# 5000A_-_-v2_-_CT100.net
KiCad netlist of a schematic drawn in EasyEDA Pro
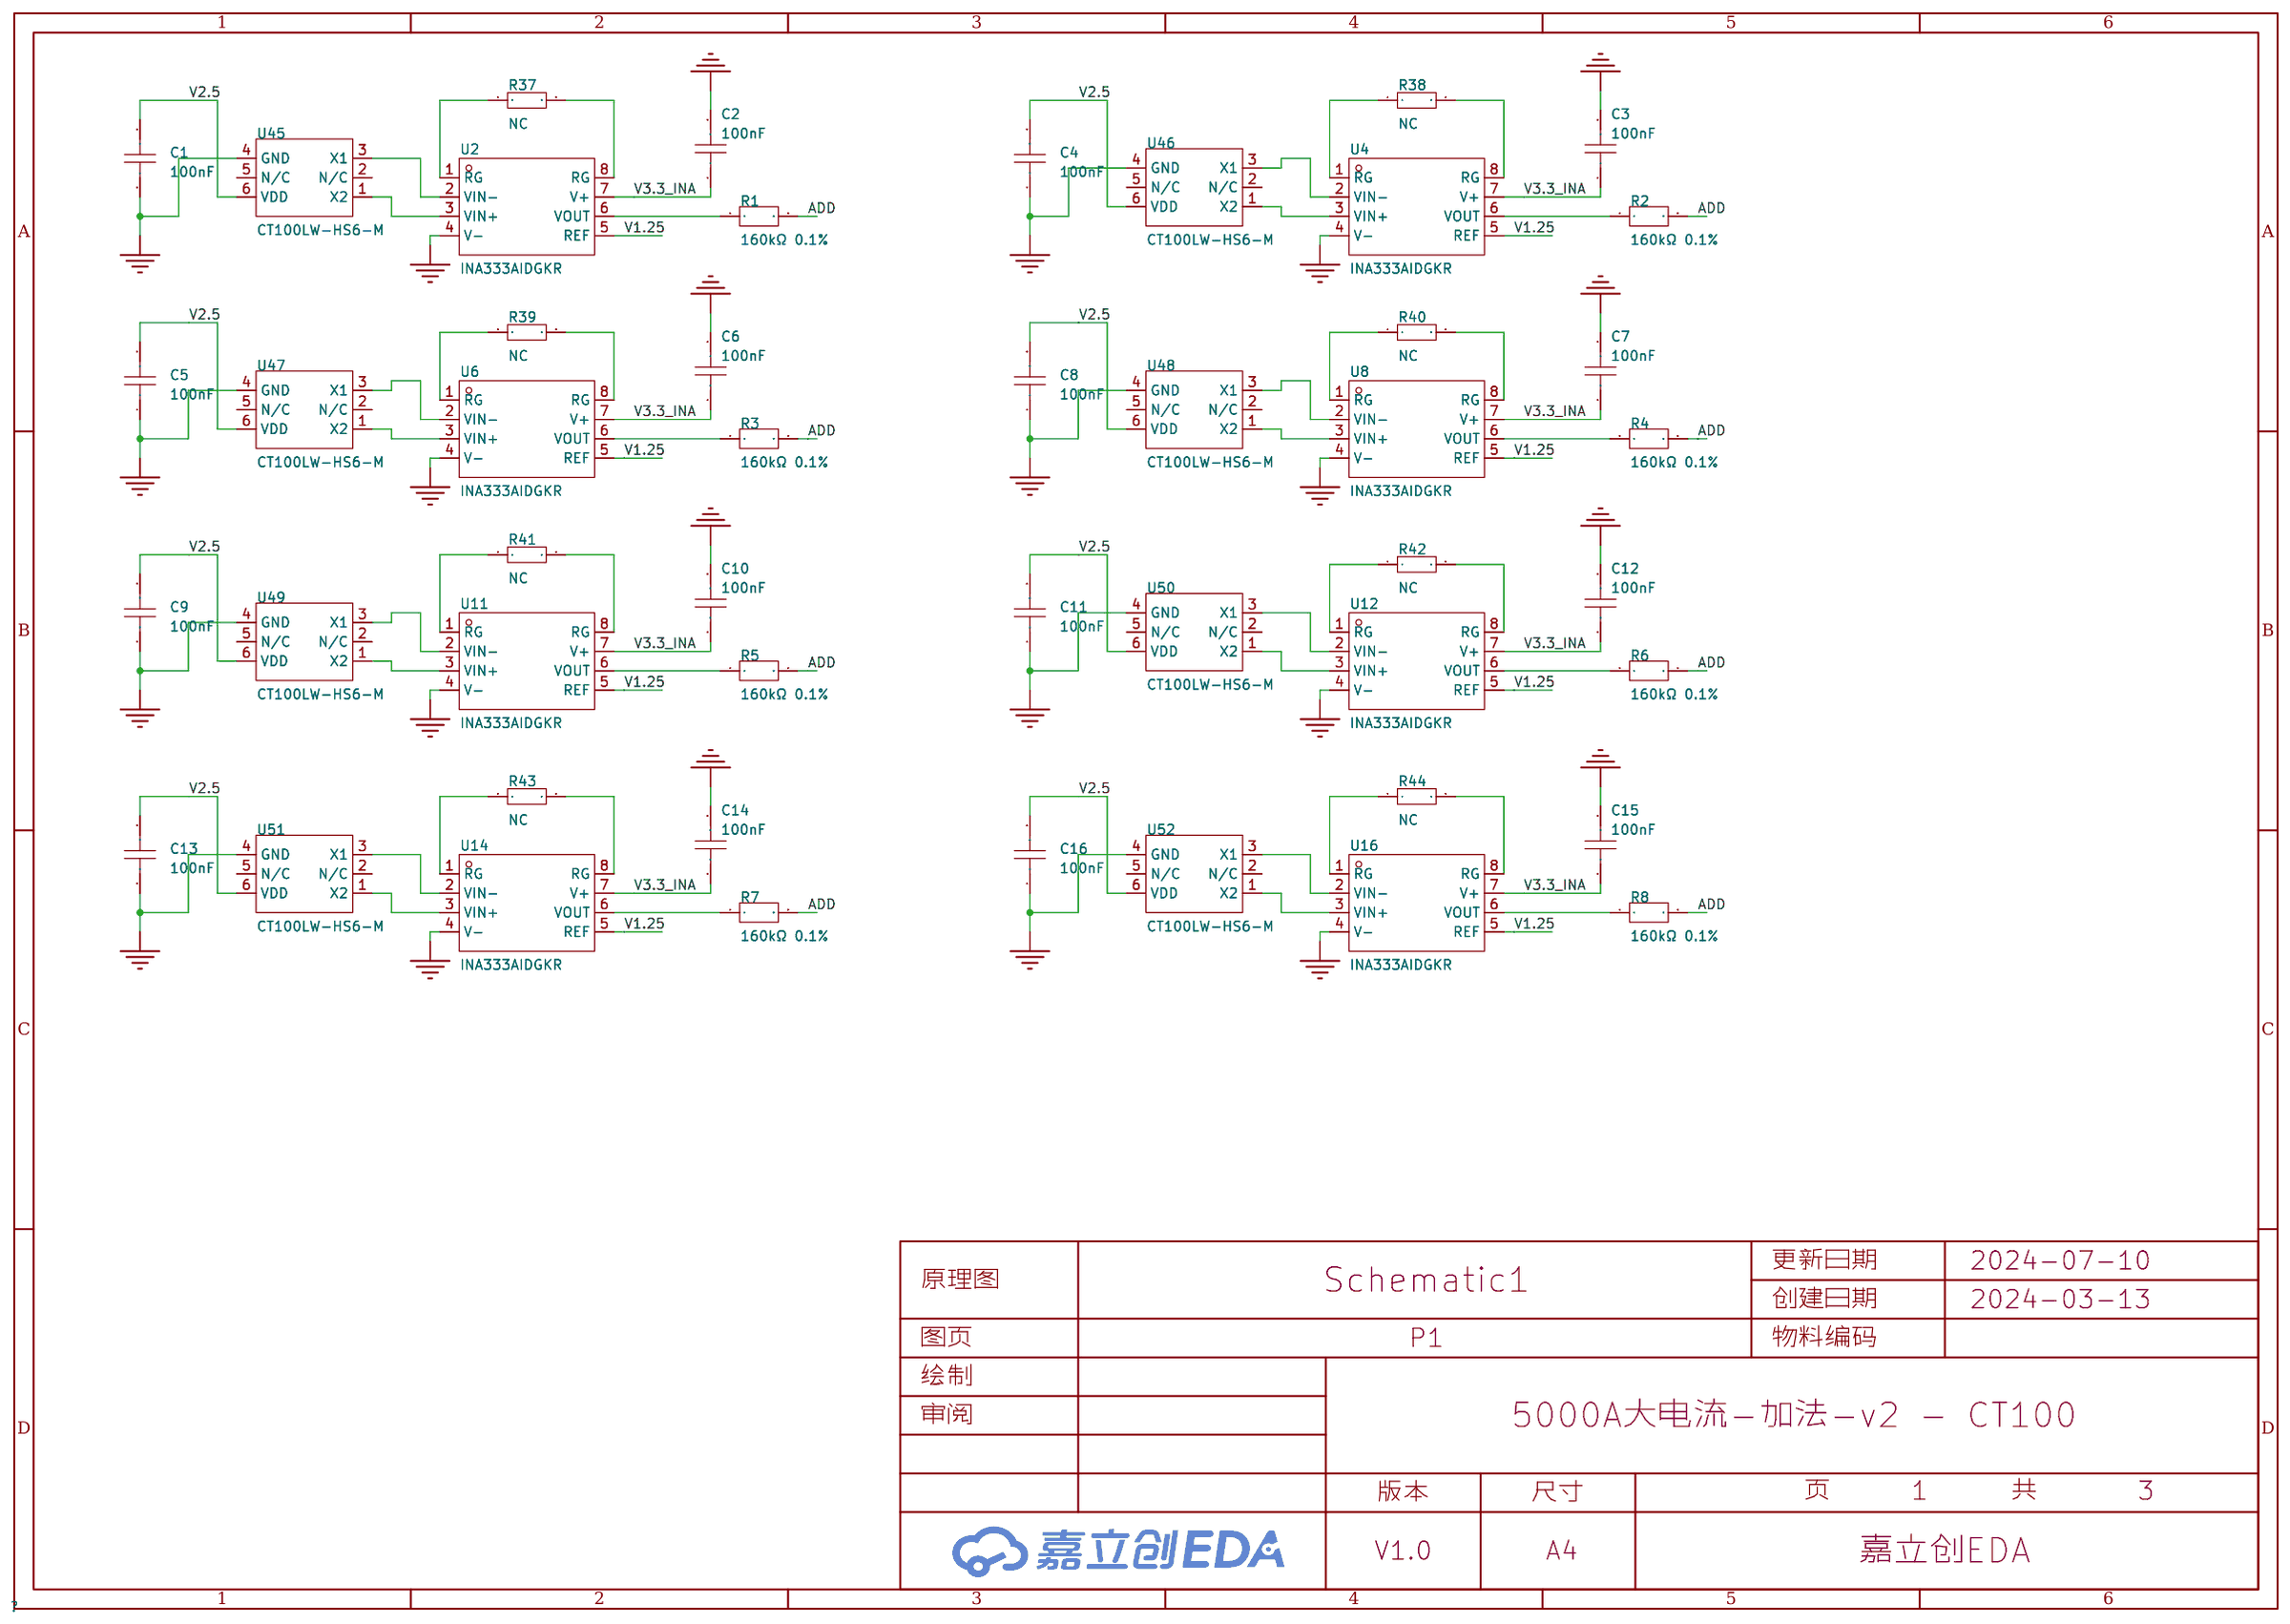
[diagram p0: P1]
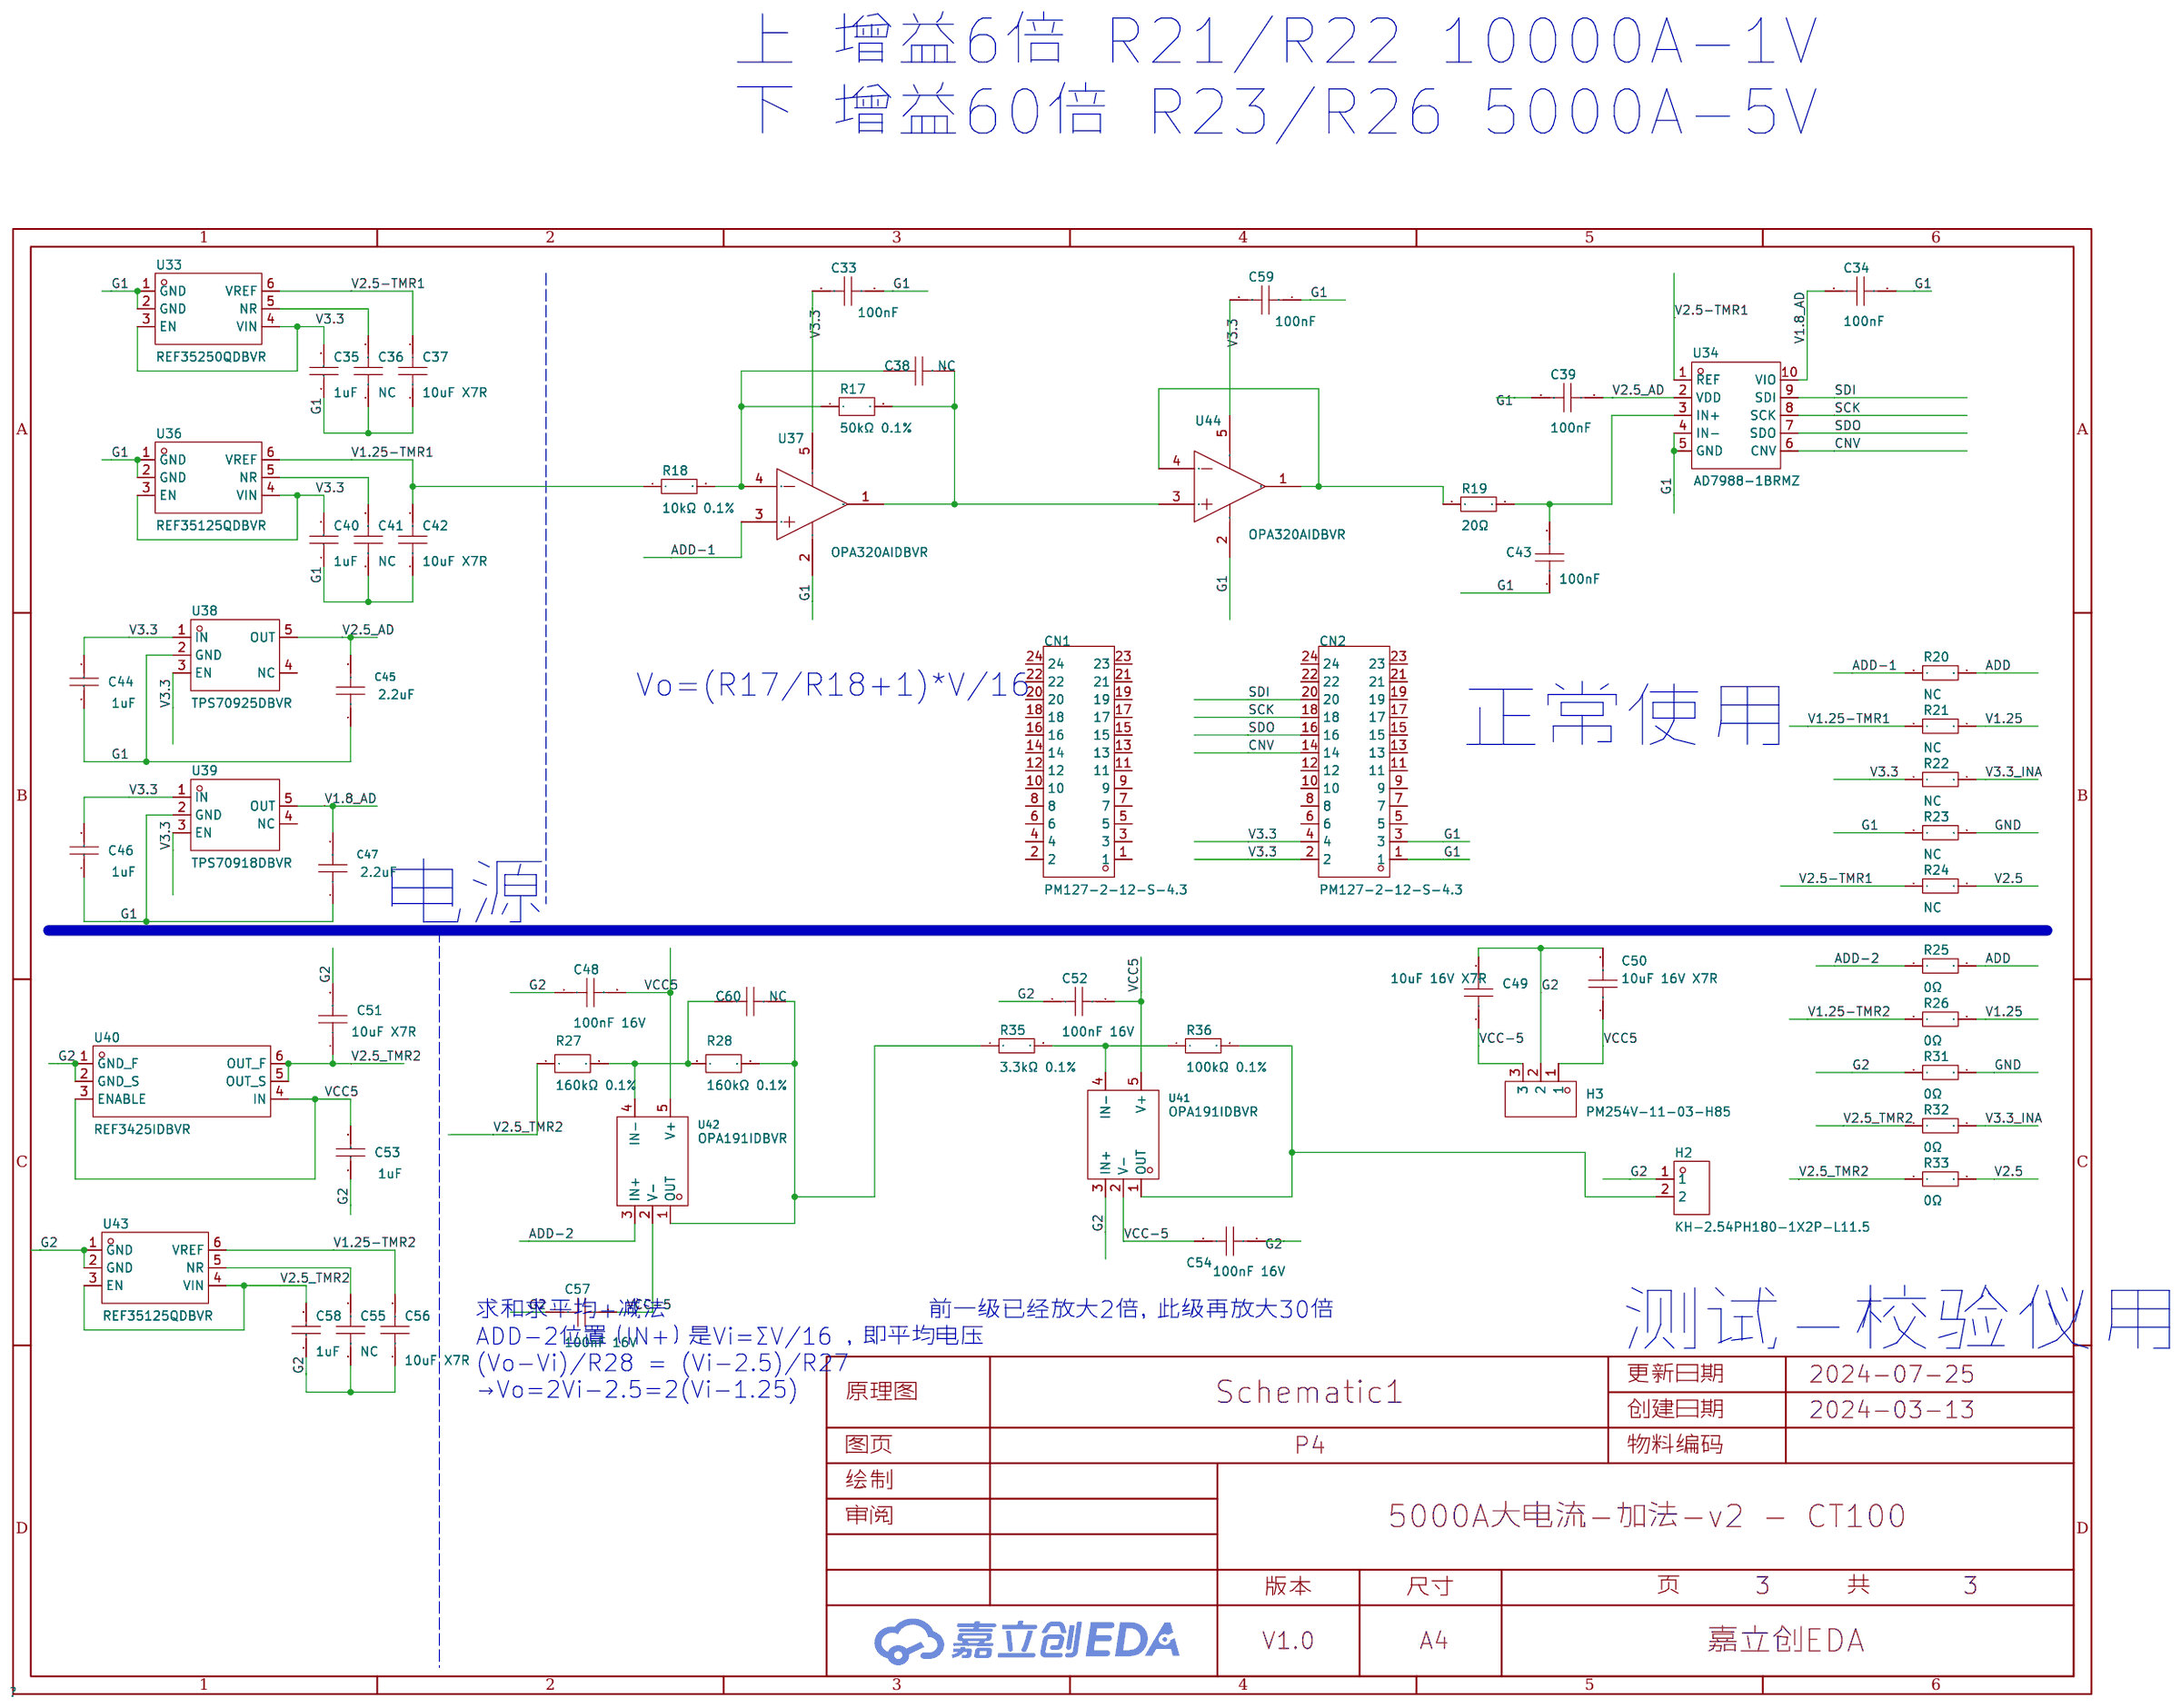
[diagram p1: P4]
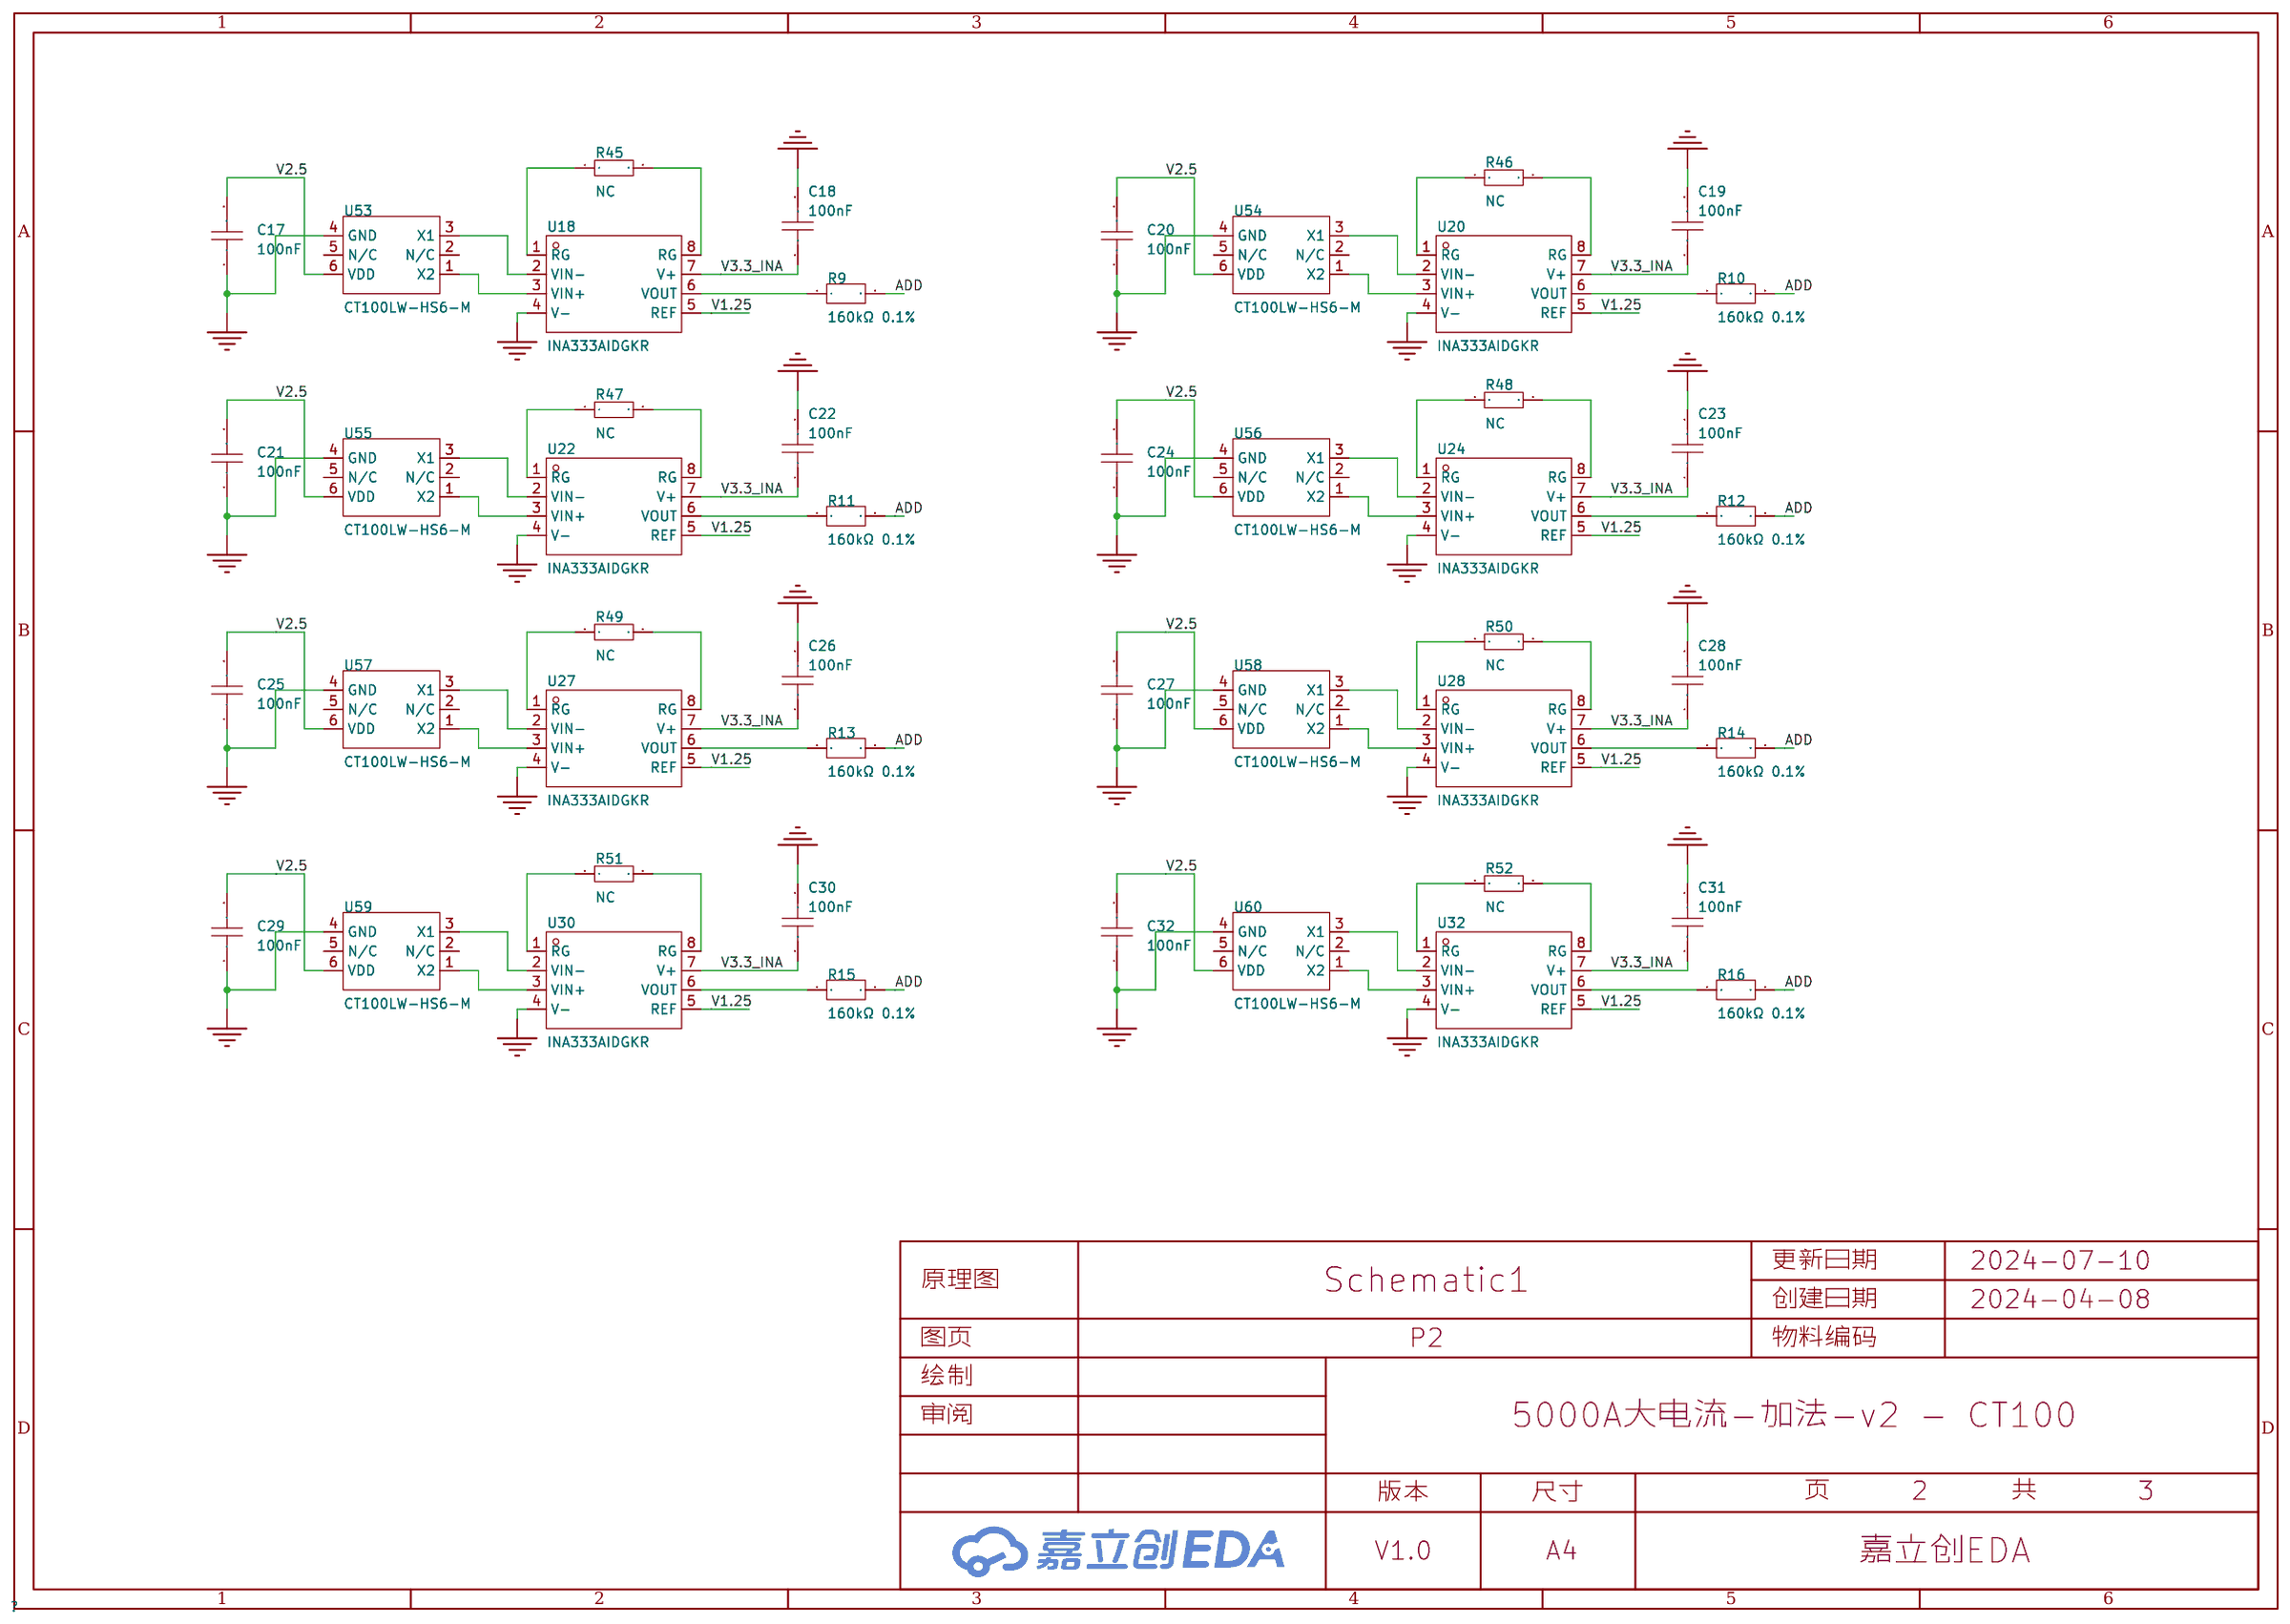
[diagram p2: P2]

(export (version "E")
  (design (tool "Eeschema 10.0.6"))
  (components
    (comp (ref "C1")
      (value "100nF")
      (footprint "easyedapro:C0603")
      (description "容值:100nF;精度:±10%;额定电压:10V;材质(温度系数):X7R;")
      (fields
        (field (name "Manufacturer Part") "CC0603KRX7R6BB104")
        (field (name "Manufacturer") "YAGEO(国巨)")
      )
      (libsource (lib "easyedapro") (part "CC0603KRX7R6BB104"))
    )
    (comp (ref "C2")
      (value "100nF")
      (footprint "easyedapro:C0603")
      (description "容值:100nF;精度:±10%;额定电压:10V;材质(温度系数):X7R;")
      (fields
        (field (name "Manufacturer Part") "CC0603KRX7R6BB104")
        (field (name "Manufacturer") "YAGEO(国巨)")
      )
      (libsource (lib "easyedapro") (part "CC0603KRX7R6BB104"))
    )
    (comp (ref "C3")
      (value "100nF")
      (footprint "easyedapro:C0603")
      (description "容值:100nF;精度:±10%;额定电压:10V;材质(温度系数):X7R;")
      (fields
        (field (name "Manufacturer Part") "CC0603KRX7R6BB104")
        (field (name "Manufacturer") "YAGEO(国巨)")
      )
      (libsource (lib "easyedapro") (part "CC0603KRX7R6BB104"))
    )
    (comp (ref "C4")
      (value "100nF")
      (footprint "easyedapro:C0603")
      (description "容值:100nF;精度:±10%;额定电压:10V;材质(温度系数):X7R;")
      (fields
        (field (name "Manufacturer Part") "CC0603KRX7R6BB104")
        (field (name "Manufacturer") "YAGEO(国巨)")
      )
      (libsource (lib "easyedapro") (part "CC0603KRX7R6BB104"))
    )
    (comp (ref "C5")
      (value "100nF")
      (footprint "easyedapro:C0603")
      (description "容值:100nF;精度:±10%;额定电压:10V;材质(温度系数):X7R;")
      (fields
        (field (name "Manufacturer Part") "CC0603KRX7R6BB104")
        (field (name "Manufacturer") "YAGEO(国巨)")
      )
      (libsource (lib "easyedapro") (part "CC0603KRX7R6BB104"))
    )
    (comp (ref "C6")
      (value "100nF")
      (footprint "easyedapro:C0603")
      (description "容值:100nF;精度:±10%;额定电压:10V;材质(温度系数):X7R;")
      (fields
        (field (name "Manufacturer Part") "CC0603KRX7R6BB104")
        (field (name "Manufacturer") "YAGEO(国巨)")
      )
      (libsource (lib "easyedapro") (part "CC0603KRX7R6BB104"))
    )
    (comp (ref "C7")
      (value "100nF")
      (footprint "easyedapro:C0603")
      (description "容值:100nF;精度:±10%;额定电压:10V;材质(温度系数):X7R;")
      (fields
        (field (name "Manufacturer Part") "CC0603KRX7R6BB104")
        (field (name "Manufacturer") "YAGEO(国巨)")
      )
      (libsource (lib "easyedapro") (part "CC0603KRX7R6BB104"))
    )
    (comp (ref "C8")
      (value "100nF")
      (footprint "easyedapro:C0603")
      (description "容值:100nF;精度:±10%;额定电压:10V;材质(温度系数):X7R;")
      (fields
        (field (name "Manufacturer Part") "CC0603KRX7R6BB104")
        (field (name "Manufacturer") "YAGEO(国巨)")
      )
      (libsource (lib "easyedapro") (part "CC0603KRX7R6BB104"))
    )
    (comp (ref "C9")
      (value "100nF")
      (footprint "easyedapro:C0603")
      (description "容值:100nF;精度:±10%;额定电压:10V;材质(温度系数):X7R;")
      (fields
        (field (name "Manufacturer Part") "CC0603KRX7R6BB104")
        (field (name "Manufacturer") "YAGEO(国巨)")
      )
      (libsource (lib "easyedapro") (part "CC0603KRX7R6BB104"))
    )
    (comp (ref "C10")
      (value "100nF")
      (footprint "easyedapro:C0603")
      (description "容值:100nF;精度:±10%;额定电压:10V;材质(温度系数):X7R;")
      (fields
        (field (name "Manufacturer Part") "CC0603KRX7R6BB104")
        (field (name "Manufacturer") "YAGEO(国巨)")
      )
      (libsource (lib "easyedapro") (part "CC0603KRX7R6BB104"))
    )
    (comp (ref "C11")
      (value "100nF")
      (footprint "easyedapro:C0603")
      (description "容值:100nF;精度:±10%;额定电压:10V;材质(温度系数):X7R;")
      (fields
        (field (name "Manufacturer Part") "CC0603KRX7R6BB104")
        (field (name "Manufacturer") "YAGEO(国巨)")
      )
      (libsource (lib "easyedapro") (part "CC0603KRX7R6BB104"))
    )
    (comp (ref "C12")
      (value "100nF")
      (footprint "easyedapro:C0603")
      (description "容值:100nF;精度:±10%;额定电压:10V;材质(温度系数):X7R;")
      (fields
        (field (name "Manufacturer Part") "CC0603KRX7R6BB104")
        (field (name "Manufacturer") "YAGEO(国巨)")
      )
      (libsource (lib "easyedapro") (part "CC0603KRX7R6BB104"))
    )
    (comp (ref "C13")
      (value "100nF")
      (footprint "easyedapro:C0603")
      (description "容值:100nF;精度:±10%;额定电压:10V;材质(温度系数):X7R;")
      (fields
        (field (name "Manufacturer Part") "CC0603KRX7R6BB104")
        (field (name "Manufacturer") "YAGEO(国巨)")
      )
      (libsource (lib "easyedapro") (part "CC0603KRX7R6BB104"))
    )
    (comp (ref "C14")
      (value "100nF")
      (footprint "easyedapro:C0603")
      (description "容值:100nF;精度:±10%;额定电压:10V;材质(温度系数):X7R;")
      (fields
        (field (name "Manufacturer Part") "CC0603KRX7R6BB104")
        (field (name "Manufacturer") "YAGEO(国巨)")
      )
      (libsource (lib "easyedapro") (part "CC0603KRX7R6BB104"))
    )
    (comp (ref "C15")
      (value "100nF")
      (footprint "easyedapro:C0603")
      (description "容值:100nF;精度:±10%;额定电压:10V;材质(温度系数):X7R;")
      (fields
        (field (name "Manufacturer Part") "CC0603KRX7R6BB104")
        (field (name "Manufacturer") "YAGEO(国巨)")
      )
      (libsource (lib "easyedapro") (part "CC0603KRX7R6BB104"))
    )
    (comp (ref "C16")
      (value "100nF")
      (footprint "easyedapro:C0603")
      (description "容值:100nF;精度:±10%;额定电压:10V;材质(温度系数):X7R;")
      (fields
        (field (name "Manufacturer Part") "CC0603KRX7R6BB104")
        (field (name "Manufacturer") "YAGEO(国巨)")
      )
      (libsource (lib "easyedapro") (part "CC0603KRX7R6BB104"))
    )
    (comp (ref "R1")
      (value "160kΩ 0.1%")
      (footprint "easyedapro:R0603")
      (description "电阻类型:薄膜电阻;阻值:160kΩ;精度:±0.1%;功率:100mW;最大工作电压:75V;温度系数:±25ppm/°C;")
      (fields (field (name "Manufacturer Part") "ERA3AEB164V") (field (name "Manufacturer") "PANASONIC(松下)"))
      (libsource (lib "easyedapro") (part "ERA3AEB164V"))
    )
    (comp (ref "R2")
      (value "160kΩ 0.1%")
      (footprint "easyedapro:R0603")
      (description "电阻类型:薄膜电阻;阻值:160kΩ;精度:±0.1%;功率:100mW;最大工作电压:75V;温度系数:±25ppm/°C;")
      (fields (field (name "Manufacturer Part") "ERA3AEB164V") (field (name "Manufacturer") "PANASONIC(松下)"))
      (libsource (lib "easyedapro") (part "ERA3AEB164V"))
    )
    (comp (ref "R3")
      (value "160kΩ 0.1%")
      (footprint "easyedapro:R0603")
      (description "电阻类型:薄膜电阻;阻值:160kΩ;精度:±0.1%;功率:100mW;最大工作电压:75V;温度系数:±25ppm/°C;")
      (fields (field (name "Manufacturer Part") "ERA3AEB164V") (field (name "Manufacturer") "PANASONIC(松下)"))
      (libsource (lib "easyedapro") (part "ERA3AEB164V"))
    )
    (comp (ref "R4")
      (value "160kΩ 0.1%")
      (footprint "easyedapro:R0603")
      (description "电阻类型:薄膜电阻;阻值:160kΩ;精度:±0.1%;功率:100mW;最大工作电压:75V;温度系数:±25ppm/°C;")
      (fields (field (name "Manufacturer Part") "ERA3AEB164V") (field (name "Manufacturer") "PANASONIC(松下)"))
      (libsource (lib "easyedapro") (part "ERA3AEB164V"))
    )
    (comp (ref "R5")
      (value "160kΩ 0.1%")
      (footprint "easyedapro:R0603")
      (description "电阻类型:薄膜电阻;阻值:160kΩ;精度:±0.1%;功率:100mW;最大工作电压:75V;温度系数:±25ppm/°C;")
      (fields (field (name "Manufacturer Part") "ERA3AEB164V") (field (name "Manufacturer") "PANASONIC(松下)"))
      (libsource (lib "easyedapro") (part "ERA3AEB164V"))
    )
    (comp (ref "R6")
      (value "160kΩ 0.1%")
      (footprint "easyedapro:R0603")
      (description "电阻类型:薄膜电阻;阻值:160kΩ;精度:±0.1%;功率:100mW;最大工作电压:75V;温度系数:±25ppm/°C;")
      (fields (field (name "Manufacturer Part") "ERA3AEB164V") (field (name "Manufacturer") "PANASONIC(松下)"))
      (libsource (lib "easyedapro") (part "ERA3AEB164V"))
    )
    (comp (ref "R7")
      (value "160kΩ 0.1%")
      (footprint "easyedapro:R0603")
      (description "电阻类型:薄膜电阻;阻值:160kΩ;精度:±0.1%;功率:100mW;最大工作电压:75V;温度系数:±25ppm/°C;")
      (fields (field (name "Manufacturer Part") "ERA3AEB164V") (field (name "Manufacturer") "PANASONIC(松下)"))
      (libsource (lib "easyedapro") (part "ERA3AEB164V"))
    )
    (comp (ref "R8")
      (value "160kΩ 0.1%")
      (footprint "easyedapro:R0603")
      (description "电阻类型:薄膜电阻;阻值:160kΩ;精度:±0.1%;功率:100mW;最大工作电压:75V;温度系数:±25ppm/°C;")
      (fields (field (name "Manufacturer Part") "ERA3AEB164V") (field (name "Manufacturer") "PANASONIC(松下)"))
      (libsource (lib "easyedapro") (part "ERA3AEB164V"))
    )
    (comp (ref "R37") (value "NC") (footprint "easyedapro:R0603") (libsource (lib "easyedapro") (part "电阻")))
    (comp (ref "R38") (value "NC") (footprint "easyedapro:R0603") (libsource (lib "easyedapro") (part "电阻")))
    (comp (ref "R39") (value "NC") (footprint "easyedapro:R0603") (libsource (lib "easyedapro") (part "电阻")))
    (comp (ref "R40") (value "NC") (footprint "easyedapro:R0603") (libsource (lib "easyedapro") (part "电阻")))
    (comp (ref "R41") (value "NC") (footprint "easyedapro:R0603") (libsource (lib "easyedapro") (part "电阻")))
    (comp (ref "R42") (value "NC") (footprint "easyedapro:R0603") (libsource (lib "easyedapro") (part "电阻")))
    (comp (ref "R43") (value "NC") (footprint "easyedapro:R0603") (libsource (lib "easyedapro") (part "电阻")))
    (comp (ref "R44") (value "NC") (footprint "easyedapro:R0603") (libsource (lib "easyedapro") (part "电阻")))
    (comp (ref "U2")
      (value "INA333AIDGKR")
      (footprint "easyedapro:MSOP-8_L3.0-W3.0-P0.65-LS5.0-BL")
      (description "放大器数:单路;输入偏置电流(Ib):70pA;输入失调电压(Vos):10uV;压摆率(SR):0.16V/us;带宽(-3db):150kHz;轨到轨:-;")
      (fields (field (name "Manufacturer") "TI(德州仪器)"))
      (libsource (lib "easyedapro") (part "INA333AIDGKR"))
    )
    (comp (ref "U4")
      (value "INA333AIDGKR")
      (footprint "easyedapro:MSOP-8_L3.0-W3.0-P0.65-LS5.0-BL")
      (description "放大器数:单路;输入偏置电流(Ib):70pA;输入失调电压(Vos):10uV;压摆率(SR):0.16V/us;带宽(-3db):150kHz;轨到轨:-;")
      (fields (field (name "Manufacturer") "TI(德州仪器)"))
      (libsource (lib "easyedapro") (part "INA333AIDGKR"))
    )
    (comp (ref "U6")
      (value "INA333AIDGKR")
      (footprint "easyedapro:MSOP-8_L3.0-W3.0-P0.65-LS5.0-BL")
      (description "放大器数:单路;输入偏置电流(Ib):70pA;输入失调电压(Vos):10uV;压摆率(SR):0.16V/us;带宽(-3db):150kHz;轨到轨:-;")
      (fields (field (name "Manufacturer") "TI(德州仪器)"))
      (libsource (lib "easyedapro") (part "INA333AIDGKR"))
    )
    (comp (ref "U8")
      (value "INA333AIDGKR")
      (footprint "easyedapro:MSOP-8_L3.0-W3.0-P0.65-LS5.0-BL")
      (description "放大器数:单路;输入偏置电流(Ib):70pA;输入失调电压(Vos):10uV;压摆率(SR):0.16V/us;带宽(-3db):150kHz;轨到轨:-;")
      (fields (field (name "Manufacturer") "TI(德州仪器)"))
      (libsource (lib "easyedapro") (part "INA333AIDGKR"))
    )
    (comp (ref "U11")
      (value "INA333AIDGKR")
      (footprint "easyedapro:MSOP-8_L3.0-W3.0-P0.65-LS5.0-BL")
      (description "放大器数:单路;输入偏置电流(Ib):70pA;输入失调电压(Vos):10uV;压摆率(SR):0.16V/us;带宽(-3db):150kHz;轨到轨:-;")
      (fields (field (name "Manufacturer") "TI(德州仪器)"))
      (libsource (lib "easyedapro") (part "INA333AIDGKR"))
    )
    (comp (ref "U12")
      (value "INA333AIDGKR")
      (footprint "easyedapro:MSOP-8_L3.0-W3.0-P0.65-LS5.0-BL")
      (description "放大器数:单路;输入偏置电流(Ib):70pA;输入失调电压(Vos):10uV;压摆率(SR):0.16V/us;带宽(-3db):150kHz;轨到轨:-;")
      (fields (field (name "Manufacturer") "TI(德州仪器)"))
      (libsource (lib "easyedapro") (part "INA333AIDGKR"))
    )
    (comp (ref "U14")
      (value "INA333AIDGKR")
      (footprint "easyedapro:MSOP-8_L3.0-W3.0-P0.65-LS5.0-BL")
      (description "放大器数:单路;输入偏置电流(Ib):70pA;输入失调电压(Vos):10uV;压摆率(SR):0.16V/us;带宽(-3db):150kHz;轨到轨:-;")
      (fields (field (name "Manufacturer") "TI(德州仪器)"))
      (libsource (lib "easyedapro") (part "INA333AIDGKR"))
    )
    (comp (ref "U16")
      (value "INA333AIDGKR")
      (footprint "easyedapro:MSOP-8_L3.0-W3.0-P0.65-LS5.0-BL")
      (description "放大器数:单路;输入偏置电流(Ib):70pA;输入失调电压(Vos):10uV;压摆率(SR):0.16V/us;带宽(-3db):150kHz;轨到轨:-;")
      (fields (field (name "Manufacturer") "TI(德州仪器)"))
      (libsource (lib "easyedapro") (part "INA333AIDGKR"))
    )
    (comp (ref "U45")
      (value "CT100LW-HS6-M")
      (footprint "easyedapro:TSOT-23-6_L2.9-W1.6-P0.95-LS2.8-BL")
      (description "工作点(Gs):-;释放点(Gs):-;")
      (fields (field (name "Manufacturer") "muRata(村田)"))
      (libsource (lib "easyedapro") (part "CT100LW-HS6-M"))
    )
    (comp (ref "U46")
      (value "CT100LW-HS6-M")
      (footprint "easyedapro:TSOT-23-6_L2.9-W1.6-P0.95-LS2.8-BL")
      (description "工作点(Gs):-;释放点(Gs):-;")
      (fields (field (name "Manufacturer") "muRata(村田)"))
      (libsource (lib "easyedapro") (part "CT100LW-HS6-M"))
    )
    (comp (ref "U47")
      (value "CT100LW-HS6-M")
      (footprint "easyedapro:TSOT-23-6_L2.9-W1.6-P0.95-LS2.8-BL")
      (description "工作点(Gs):-;释放点(Gs):-;")
      (fields (field (name "Manufacturer") "muRata(村田)"))
      (libsource (lib "easyedapro") (part "CT100LW-HS6-M"))
    )
    (comp (ref "U48")
      (value "CT100LW-HS6-M")
      (footprint "easyedapro:TSOT-23-6_L2.9-W1.6-P0.95-LS2.8-BL")
      (description "工作点(Gs):-;释放点(Gs):-;")
      (fields (field (name "Manufacturer") "muRata(村田)"))
      (libsource (lib "easyedapro") (part "CT100LW-HS6-M"))
    )
    (comp (ref "U49")
      (value "CT100LW-HS6-M")
      (footprint "easyedapro:TSOT-23-6_L2.9-W1.6-P0.95-LS2.8-BL")
      (description "工作点(Gs):-;释放点(Gs):-;")
      (fields (field (name "Manufacturer") "muRata(村田)"))
      (libsource (lib "easyedapro") (part "CT100LW-HS6-M"))
    )
    (comp (ref "U50")
      (value "CT100LW-HS6-M")
      (footprint "easyedapro:TSOT-23-6_L2.9-W1.6-P0.95-LS2.8-BL")
      (description "工作点(Gs):-;释放点(Gs):-;")
      (fields (field (name "Manufacturer") "muRata(村田)"))
      (libsource (lib "easyedapro") (part "CT100LW-HS6-M"))
    )
    (comp (ref "U51")
      (value "CT100LW-HS6-M")
      (footprint "easyedapro:TSOT-23-6_L2.9-W1.6-P0.95-LS2.8-BL")
      (description "工作点(Gs):-;释放点(Gs):-;")
      (fields (field (name "Manufacturer") "muRata(村田)"))
      (libsource (lib "easyedapro") (part "CT100LW-HS6-M"))
    )
    (comp (ref "U52")
      (value "CT100LW-HS6-M")
      (footprint "easyedapro:TSOT-23-6_L2.9-W1.6-P0.95-LS2.8-BL")
      (description "工作点(Gs):-;释放点(Gs):-;")
      (fields (field (name "Manufacturer") "muRata(村田)"))
      (libsource (lib "easyedapro") (part "CT100LW-HS6-M"))
    )
    (comp (ref "C33")
      (value "100nF")
      (footprint "easyedapro:C0603")
      (description "容值:100nF;精度:±10%;额定电压:10V;材质(温度系数):X7R;")
      (fields
        (field (name "Manufacturer Part") "CC0603KRX7R6BB104")
        (field (name "Manufacturer") "YAGEO(国巨)")
      )
      (libsource (lib "easyedapro") (part "CC0603KRX7R6BB104"))
    )
    (comp (ref "C34")
      (value "100nF")
      (footprint "easyedapro:C0603")
      (description "容值:100nF;精度:±10%;额定电压:10V;材质(温度系数):X7R;")
      (fields
        (field (name "Manufacturer Part") "CC0603KRX7R6BB104")
        (field (name "Manufacturer") "YAGEO(国巨)")
      )
      (libsource (lib "easyedapro") (part "CC0603KRX7R6BB104"))
    )
    (comp (ref "C35")
      (value "1uF")
      (footprint "easyedapro:C0603")
      (description "容值:1uF;精度:±10%;额定电压:25V;材质(温度系数):X7R;")
      (fields (field (name "Manufacturer Part") "0603B105K250NT") (field (name "Manufacturer") "FH(风华)"))
      (libsource (lib "easyedapro") (part "0603B105K250NT"))
    )
    (comp (ref "C36")
      (value "NC")
      (footprint "easyedapro:C0603")
      (description "容值:10uF;精度:±10%;额定电压:10V;材质(温度系数):X7R;")
      (fields
        (field (name "Manufacturer Part") "GRM188Z71A106KA73D")
        (field (name "Manufacturer") "muRata(村田)")
      )
      (libsource (lib "easyedapro") (part "GRM188Z71A106KA73D"))
    )
    (comp (ref "C37")
      (value "10uF X7R")
      (footprint "easyedapro:C0603")
      (description "容值:10uF;精度:±10%;额定电压:10V;材质(温度系数):X7R;")
      (fields
        (field (name "Manufacturer Part") "GRM188Z71A106KA73D")
        (field (name "Manufacturer") "muRata(村田)")
      )
      (libsource (lib "easyedapro") (part "GRM188Z71A106KA73D"))
    )
    (comp (ref "C38")
      (value "NC")
      (footprint "easyedapro:C0603")
      (libsource (lib "easyedapro") (part "CapAcitance"))
    )
    (comp (ref "C39")
      (value "100nF")
      (footprint "easyedapro:C0603")
      (description "容值:100nF;精度:±10%;额定电压:10V;材质(温度系数):X7R;")
      (fields
        (field (name "Manufacturer Part") "CC0603KRX7R6BB104")
        (field (name "Manufacturer") "YAGEO(国巨)")
      )
      (libsource (lib "easyedapro") (part "CC0603KRX7R6BB104"))
    )
    (comp (ref "C40")
      (value "1uF")
      (footprint "easyedapro:C0603")
      (description "容值:1uF;精度:±10%;额定电压:25V;材质(温度系数):X7R;")
      (fields (field (name "Manufacturer Part") "0603B105K250NT") (field (name "Manufacturer") "FH(风华)"))
      (libsource (lib "easyedapro") (part "0603B105K250NT"))
    )
    (comp (ref "C41")
      (value "NC")
      (footprint "easyedapro:C0603")
      (description "容值:10uF;精度:±10%;额定电压:10V;材质(温度系数):X7R;")
      (fields
        (field (name "Manufacturer Part") "GRM188Z71A106KA73D")
        (field (name "Manufacturer") "muRata(村田)")
      )
      (libsource (lib "easyedapro") (part "GRM188Z71A106KA73D"))
    )
    (comp (ref "C42")
      (value "10uF X7R")
      (footprint "easyedapro:C0603")
      (description "容值:10uF;精度:±10%;额定电压:10V;材质(温度系数):X7R;")
      (fields
        (field (name "Manufacturer Part") "GRM188Z71A106KA73D")
        (field (name "Manufacturer") "muRata(村田)")
      )
      (libsource (lib "easyedapro") (part "GRM188Z71A106KA73D"))
    )
    (comp (ref "C43")
      (value "100nF")
      (footprint "easyedapro:C0603")
      (description "容值:100nF;精度:±10%;额定电压:10V;材质(温度系数):X7R;")
      (fields
        (field (name "Manufacturer Part") "CC0603KRX7R6BB104")
        (field (name "Manufacturer") "YAGEO(国巨)")
      )
      (libsource (lib "easyedapro") (part "CC0603KRX7R6BB104"))
    )
    (comp (ref "C44")
      (value "1uF")
      (footprint "easyedapro:C0603")
      (description "容值:1uF;精度:±10%;额定电压:25V;材质(温度系数):X7R;")
      (fields (field (name "Manufacturer Part") "0603B105K250NT") (field (name "Manufacturer") "FH(风华)"))
      (libsource (lib "easyedapro") (part "0603B105K250NT"))
    )
    (comp (ref "C45")
      (value "2.2uF")
      (footprint "easyedapro:C0603")
      (description "容值:2.2uF;精度:±10%;额定电压:50V;材质(温度系数):X5R;")
      (fields
        (field (name "Manufacturer Part") "CL10A225KB8NNNC")
        (field (name "Manufacturer") "SAMSUNG(三星)")
      )
      (libsource (lib "easyedapro") (part "CL10A225KB8NNNC"))
    )
    (comp (ref "C46")
      (value "1uF")
      (footprint "easyedapro:C0603")
      (description "容值:1uF;精度:±10%;额定电压:25V;材质(温度系数):X7R;")
      (fields (field (name "Manufacturer Part") "0603B105K250NT") (field (name "Manufacturer") "FH(风华)"))
      (libsource (lib "easyedapro") (part "0603B105K250NT"))
    )
    (comp (ref "C47")
      (value "2.2uF")
      (footprint "easyedapro:C0603")
      (description "容值:2.2uF;精度:±10%;额定电压:50V;材质(温度系数):X5R;")
      (fields
        (field (name "Manufacturer Part") "CL10A225KB8NNNC")
        (field (name "Manufacturer") "SAMSUNG(三星)")
      )
      (libsource (lib "easyedapro") (part "CL10A225KB8NNNC"))
    )
    (comp (ref "C48")
      (value "100nF 16V")
      (footprint "easyedapro:C0603")
      (description "容值:100nF;精度:±10%;额定电压:10V;材质(温度系数):X7R;")
      (fields
        (field (name "Manufacturer Part") "CC0603KRX7R6BB104")
        (field (name "Manufacturer") "YAGEO(国巨)")
      )
      (libsource (lib "easyedapro") (part "CC0603KRX7R6BB104"))
    )
    (comp (ref "C49")
      (value "10uF 16V X7R")
      (footprint "easyedapro:C0603")
      (description "容值:10uF;精度:±10%;额定电压:10V;材质(温度系数):X7R;")
      (fields
        (field (name "Manufacturer Part") "GRM188Z71A106KA73D")
        (field (name "Manufacturer") "muRata(村田)")
      )
      (libsource (lib "easyedapro") (part "GRM188Z71A106KA73D"))
    )
    (comp (ref "C50")
      (value "10uF 16V X7R")
      (footprint "easyedapro:C0603")
      (description "容值:10uF;精度:±10%;额定电压:10V;材质(温度系数):X7R;")
      (fields
        (field (name "Manufacturer Part") "GRM188Z71A106KA73D")
        (field (name "Manufacturer") "muRata(村田)")
      )
      (libsource (lib "easyedapro") (part "GRM188Z71A106KA73D"))
    )
    (comp (ref "C51")
      (value "10uF X7R")
      (footprint "easyedapro:C0603")
      (description "容值:10uF;精度:±10%;额定电压:10V;材质(温度系数):X7R;")
      (fields
        (field (name "Manufacturer Part") "GRM188Z71A106KA73D")
        (field (name "Manufacturer") "muRata(村田)")
      )
      (libsource (lib "easyedapro") (part "GRM188Z71A106KA73D"))
    )
    (comp (ref "C52")
      (value "100nF 16V")
      (footprint "easyedapro:C0603")
      (description "容值:100nF;精度:±10%;额定电压:10V;材质(温度系数):X7R;")
      (fields
        (field (name "Manufacturer Part") "CC0603KRX7R6BB104")
        (field (name "Manufacturer") "YAGEO(国巨)")
      )
      (libsource (lib "easyedapro") (part "CC0603KRX7R6BB104"))
    )
    (comp (ref "C53")
      (value "1uF")
      (footprint "easyedapro:C0603")
      (description "容值:1uF;精度:±10%;额定电压:25V;材质(温度系数):X7R;")
      (fields (field (name "Manufacturer Part") "0603B105K250NT") (field (name "Manufacturer") "FH(风华)"))
      (libsource (lib "easyedapro") (part "0603B105K250NT"))
    )
    (comp (ref "C54")
      (value "100nF 16V")
      (footprint "easyedapro:C0603")
      (description "容值:100nF;精度:±10%;额定电压:10V;材质(温度系数):X7R;")
      (fields
        (field (name "Manufacturer Part") "CC0603KRX7R6BB104")
        (field (name "Manufacturer") "YAGEO(国巨)")
      )
      (libsource (lib "easyedapro") (part "CC0603KRX7R6BB104"))
    )
    (comp (ref "C55")
      (value "NC")
      (footprint "easyedapro:C0603")
      (description "容值:10uF;精度:±10%;额定电压:10V;材质(温度系数):X7R;")
      (fields
        (field (name "Manufacturer Part") "GRM188Z71A106KA73D")
        (field (name "Manufacturer") "muRata(村田)")
      )
      (libsource (lib "easyedapro") (part "GRM188Z71A106KA73D"))
    )
    (comp (ref "C56")
      (value "10uF X7R")
      (footprint "easyedapro:C0603")
      (description "容值:10uF;精度:±10%;额定电压:10V;材质(温度系数):X7R;")
      (fields
        (field (name "Manufacturer Part") "GRM188Z71A106KA73D")
        (field (name "Manufacturer") "muRata(村田)")
      )
      (libsource (lib "easyedapro") (part "GRM188Z71A106KA73D"))
    )
    (comp (ref "C57")
      (value "100nF 16V")
      (footprint "easyedapro:C0603")
      (description "容值:100nF;精度:±10%;额定电压:10V;材质(温度系数):X7R;")
      (fields
        (field (name "Manufacturer Part") "CC0603KRX7R6BB104")
        (field (name "Manufacturer") "YAGEO(国巨)")
      )
      (libsource (lib "easyedapro") (part "CC0603KRX7R6BB104"))
    )
    (comp (ref "C58")
      (value "1uF")
      (footprint "easyedapro:C0603")
      (description "容值:1uF;精度:±10%;额定电压:25V;材质(温度系数):X7R;")
      (fields (field (name "Manufacturer Part") "0603B105K250NT") (field (name "Manufacturer") "FH(风华)"))
      (libsource (lib "easyedapro") (part "0603B105K250NT"))
    )
    (comp (ref "C59")
      (value "100nF")
      (footprint "easyedapro:C0603")
      (description "容值:100nF;精度:±10%;额定电压:10V;材质(温度系数):X7R;")
      (fields
        (field (name "Manufacturer Part") "CC0603KRX7R6BB104")
        (field (name "Manufacturer") "YAGEO(国巨)")
      )
      (libsource (lib "easyedapro") (part "CC0603KRX7R6BB104"))
    )
    (comp (ref "C60")
      (value "NC")
      (footprint "easyedapro:C0603")
      (libsource (lib "easyedapro") (part "CapAcitance"))
    )
    (comp (ref "CN1")
      (value "PM127-2-12-S-4.3")
      (footprint "easyedapro:HDR-SMD_24P-P1.27-V-F-R2-C12-LS4.8")
      (fields (field (name "Manufacturer") "HCTL(华灿天禄)"))
      (libsource (lib "easyedapro") (part "PM127-2-12-S-4.3"))
    )
    (comp (ref "CN2")
      (value "PM127-2-12-S-4.3")
      (footprint "easyedapro:HDR-SMD_24P-P1.27-V-F-R2-C12-LS4.8")
      (fields (field (name "Manufacturer") "HCTL(华灿天禄)"))
      (libsource (lib "easyedapro") (part "PM127-2-12-S-4.3"))
    )
    (comp (ref "H2")
      (value "KH-2.54PH180-1X2P-L11.5")
      (footprint "easyedapro:HDR-TH_2P-P2.54-V-M")
      (fields (field (name "Manufacturer") "kinghelm(金航标)"))
      (libsource (lib "easyedapro") (part "KH-2.54PH180-1X2P-L11.5"))
    )
    (comp (ref "H3")
      (value "PM254V-11-03-H85")
      (footprint "easyedapro:HDR-TH_3P-P2.54-V-F")
      (description "插孔结构:1x3P;间距:2.54mm;行距:-;安装类型:直插;排数:单排;总孔位数:3P;塑高:-;触头材质:黄铜;触头镀层:-;")
      (fields (field (name "Manufacturer") "XFCN(兴飞)"))
      (libsource (lib "easyedapro") (part "PM254V-11-03-H85"))
    )
    (comp (ref "R17")
      (value "50kΩ 0.1%")
      (footprint "easyedapro:R0603")
      (description "电阻类型:薄膜电阻;阻值:50kΩ;精度:±0.1%;功率:100mW;最大工作电压:-;温度系数:±25ppm/°C;")
      (fields (field (name "Manufacturer Part") "RT0603BRD0750KL") (field (name "Manufacturer") "YAGEO(国巨)"))
      (libsource (lib "easyedapro") (part "RT0603BRD0750KL"))
    )
    (comp (ref "R18")
      (value "10kΩ 0.1%")
      (footprint "easyedapro:R0603")
      (description "电阻类型:薄膜电阻;阻值:10kΩ;精度:±0.1%;功率:100mW;最大工作电压:75V;温度系数:±25ppm/°C;")
      (fields (field (name "Manufacturer Part") "RT0603BRD0710KL") (field (name "Manufacturer") "YAGEO(国巨)"))
      (libsource (lib "easyedapro") (part "RT0603BRD0710KL"))
    )
    (comp (ref "R19")
      (value "20Ω")
      (footprint "easyedapro:R0603")
      (description "电阻类型:厚膜电阻;阻值:20Ω;精度:±1%;功率:100mW;最大工作电压:75V;温度系数:±100ppm/°C;")
      (fields (field (name "Manufacturer Part") "RC0603FR-0720RL") (field (name "Manufacturer") "YAGEO(国巨)"))
      (libsource (lib "easyedapro") (part "RC0603FR-0720RL"))
    )
    (comp (ref "R20")
      (value "NC")
      (footprint "easyedapro:R0603")
      (description "电阻类型:厚膜电阻;阻值:0Ω;精度:±1%;功率:100mW;最大工作电压:75V;")
      (fields
        (field (name "Manufacturer Part") "0603WAF0000T5E")
        (field (name "Manufacturer") "UNI-ROYAL(厚声)")
      )
      (libsource (lib "easyedapro") (part "0603WAF0000T5E"))
    )
    (comp (ref "R21")
      (value "NC")
      (footprint "easyedapro:R0603")
      (description "电阻类型:厚膜电阻;阻值:0Ω;精度:±1%;功率:100mW;最大工作电压:75V;")
      (fields
        (field (name "Manufacturer Part") "0603WAF0000T5E")
        (field (name "Manufacturer") "UNI-ROYAL(厚声)")
      )
      (libsource (lib "easyedapro") (part "0603WAF0000T5E"))
    )
    (comp (ref "R22")
      (value "NC")
      (footprint "easyedapro:R0603")
      (description "电阻类型:厚膜电阻;阻值:0Ω;精度:±1%;功率:100mW;最大工作电压:75V;")
      (fields
        (field (name "Manufacturer Part") "0603WAF0000T5E")
        (field (name "Manufacturer") "UNI-ROYAL(厚声)")
      )
      (libsource (lib "easyedapro") (part "0603WAF0000T5E"))
    )
    (comp (ref "R23")
      (value "NC")
      (footprint "easyedapro:R0603")
      (description "电阻类型:厚膜电阻;阻值:0Ω;精度:±1%;功率:100mW;最大工作电压:75V;")
      (fields
        (field (name "Manufacturer Part") "0603WAF0000T5E")
        (field (name "Manufacturer") "UNI-ROYAL(厚声)")
      )
      (libsource (lib "easyedapro") (part "0603WAF0000T5E"))
    )
    (comp (ref "R24")
      (value "NC")
      (footprint "easyedapro:R0603")
      (description "电阻类型:厚膜电阻;阻值:0Ω;精度:±1%;功率:100mW;最大工作电压:75V;")
      (fields
        (field (name "Manufacturer Part") "0603WAF0000T5E")
        (field (name "Manufacturer") "UNI-ROYAL(厚声)")
      )
      (libsource (lib "easyedapro") (part "0603WAF0000T5E"))
    )
    (comp (ref "R25")
      (value "0Ω")
      (footprint "easyedapro:R0603")
      (description "电阻类型:厚膜电阻;阻值:0Ω;精度:±1%;功率:100mW;最大工作电压:75V;")
      (fields
        (field (name "Manufacturer Part") "0603WAF0000T5E")
        (field (name "Manufacturer") "UNI-ROYAL(厚声)")
      )
      (libsource (lib "easyedapro") (part "0603WAF0000T5E"))
    )
    (comp (ref "R26")
      (value "0Ω")
      (footprint "easyedapro:R0603")
      (description "电阻类型:厚膜电阻;阻值:0Ω;精度:±1%;功率:100mW;最大工作电压:75V;")
      (fields
        (field (name "Manufacturer Part") "0603WAF0000T5E")
        (field (name "Manufacturer") "UNI-ROYAL(厚声)")
      )
      (libsource (lib "easyedapro") (part "0603WAF0000T5E"))
    )
    (comp (ref "R27")
      (value "160kΩ 0.1%")
      (footprint "easyedapro:R0603")
      (description "电阻类型:薄膜电阻;阻值:160kΩ;精度:±0.1%;功率:100mW;最大工作电压:75V;温度系数:±25ppm/°C;")
      (fields (field (name "Manufacturer Part") "ERA3AEB164V") (field (name "Manufacturer") "PANASONIC(松下)"))
      (libsource (lib "easyedapro") (part "ERA3AEB164V"))
    )
    (comp (ref "R28")
      (value "160kΩ 0.1%")
      (footprint "easyedapro:R0603")
      (description "电阻类型:薄膜电阻;阻值:160kΩ;精度:±0.1%;功率:100mW;最大工作电压:75V;温度系数:±25ppm/°C;")
      (fields (field (name "Manufacturer Part") "ERA3AEB164V") (field (name "Manufacturer") "PANASONIC(松下)"))
      (libsource (lib "easyedapro") (part "ERA3AEB164V"))
    )
    (comp (ref "R31")
      (value "0Ω")
      (footprint "easyedapro:R0603")
      (description "电阻类型:厚膜电阻;阻值:0Ω;精度:±1%;功率:100mW;最大工作电压:75V;")
      (fields
        (field (name "Manufacturer Part") "0603WAF0000T5E")
        (field (name "Manufacturer") "UNI-ROYAL(厚声)")
      )
      (libsource (lib "easyedapro") (part "0603WAF0000T5E"))
    )
    (comp (ref "R32")
      (value "0Ω")
      (footprint "easyedapro:R0603")
      (description "电阻类型:厚膜电阻;阻值:0Ω;精度:±1%;功率:100mW;最大工作电压:75V;")
      (fields
        (field (name "Manufacturer Part") "0603WAF0000T5E")
        (field (name "Manufacturer") "UNI-ROYAL(厚声)")
      )
      (libsource (lib "easyedapro") (part "0603WAF0000T5E"))
    )
    (comp (ref "R33")
      (value "0Ω")
      (footprint "easyedapro:R0603")
      (description "电阻类型:厚膜电阻;阻值:0Ω;精度:±1%;功率:100mW;最大工作电压:75V;")
      (fields
        (field (name "Manufacturer Part") "0603WAF0000T5E")
        (field (name "Manufacturer") "UNI-ROYAL(厚声)")
      )
      (libsource (lib "easyedapro") (part "0603WAF0000T5E"))
    )
    (comp (ref "R35")
      (value "3.3kΩ 0.1%")
      (footprint "easyedapro:R0603")
      (description "电阻类型:薄膜电阻;阻值:3.3kΩ;精度:±0.1%;功率:100mW;最大工作电压:75V;温度系数:±25ppm/°C;")
      (fields (field (name "Manufacturer Part") "RT0603BRD073K3L") (field (name "Manufacturer") "YAGEO(国巨)"))
      (libsource (lib "easyedapro") (part "RT0603BRD073K3L"))
    )
    (comp (ref "R36")
      (value "100kΩ 0.1%")
      (footprint "easyedapro:R0603")
      (description "电阻类型:薄膜电阻;阻值:100kΩ;精度:±0.1%;功率:100mW;最大工作电压:75V;温度系数:±25ppm/°C;")
      (fields (field (name "Manufacturer Part") "RT0603BRD07100KL") (field (name "Manufacturer") "YAGEO(国巨)"))
      (libsource (lib "easyedapro") (part "RT0603BRD07100KL"))
    )
    (comp (ref "U33")
      (value "REF35250QDBVR")
      (footprint "easyedapro:SOT-23-6_L2.9-W1.6-P0.95-LS2.8-TL")
      (description "输出类型:固定;输入电压:2.75V~6V;输出电压:2.5V;输出电流:10mA;精度:±0.05%;")
      (fields (field (name "Manufacturer") "TI(德州仪器)"))
      (libsource (lib "easyedapro") (part "REF35250QDBVR"))
    )
    (comp (ref "U34")
      (value "AD7988-1BRMZ")
      (footprint "easyedapro:MSOP-10_L3.0-W3.0-P0.50-LS4.9-BL")
      (description "接口:SPI；DSP;电源电压:2.375V~2.625V;采样率:100kHz;分辨率:16位;")
      (fields (field (name "Manufacturer") "ADI(亚德诺)"))
      (libsource (lib "easyedapro") (part "AD7988-1BRMZ"))
    )
    (comp (ref "U36")
      (value "REF35125QDBVR")
      (footprint "easyedapro:SOT-23-6_L2.9-W1.6-P0.95-LS2.8-BR")
      (description "输出类型:固定;输入电压:1.5V~6V;输出电压:1.25V;输出电流:10mA;精度:±0.05%;")
      (fields (field (name "Manufacturer") "TI(德州仪器)"))
      (libsource (lib "easyedapro") (part "REF35125QDBVR"))
    )
    (comp (ref "U37")
      (value "OPA320AIDBVR")
      (footprint "easyedapro:SOT-23-5_L3.0-W1.7-P0.95-LS2.8-BR")
      (description "放大器数:单路;增益带宽积(GBP):20MHz;输入偏置电流(Ib):0.2pA;压摆率(SR):10V/us;轨到轨:-;")
      (fields (field (name "Manufacturer") "TI(德州仪器)"))
      (libsource (lib "easyedapro") (part "OPA320AIDBVR"))
    )
    (comp (ref "U38")
      (value "TPS70925DBVR")
      (footprint "easyedapro:SOT-23-5_L3.0-W1.7-P0.95-LS2.8-BL")
      (description "输出类型:固定;最大输入电压:30V;输出电压:2.5V;最大输出电流:150mA;输出极性:正极;")
      (fields (field (name "Manufacturer") "TI(德州仪器)"))
      (libsource (lib "easyedapro") (part "TPS70925DBVR"))
    )
    (comp (ref "U39")
      (value "TPS70918DBVR")
      (footprint "easyedapro:SOT-23-5_L3.0-W1.7-P0.95-LS2.8-BL")
      (description "输出类型:固定;最大输入电压:30V;输出电压:1.8V;最大输出电流:150mA;输出极性:正极;")
      (fields (field (name "Manufacturer") "TI(德州仪器)"))
      (libsource (lib "easyedapro") (part "TPS70918DBVR"))
    )
    (comp (ref "U40")
      (value "REF3425IDBVR")
      (footprint "easyedapro:SOT-23-6_L2.9-W1.6-P0.95-LS2.8-BR")
      (description "输出类型:固定;输入电压:3V~12V;输出电压:2.5V;输出电流:10mA;精度:±0.05%;")
      (fields (field (name "Manufacturer") "TI(德州仪器)"))
      (libsource (lib "easyedapro") (part "REF3425IDBVR"))
    )
    (comp (ref "U41")
      (value "OPA191IDBVR")
      (footprint "easyedapro:SOT-23-5_L2.9-W1.6-P0.95-LS2.8-BL")
      (description "放大器数:单路;增益带宽积(GBP):2.5MHz;输入偏置电流(Ib):5pA;压摆率(SR):5.5V/us;轨到轨:-;")
      (fields (field (name "Manufacturer") "TI(德州仪器)"))
      (libsource (lib "easyedapro") (part "OPA191IDBVR"))
    )
    (comp (ref "U42")
      (value "OPA191IDBVR")
      (footprint "easyedapro:SOT-23-5_L2.9-W1.6-P0.95-LS2.8-BL")
      (description "放大器数:单路;增益带宽积(GBP):2.5MHz;输入偏置电流(Ib):5pA;压摆率(SR):5.5V/us;轨到轨:-;")
      (fields (field (name "Manufacturer") "TI(德州仪器)"))
      (libsource (lib "easyedapro") (part "OPA191IDBVR"))
    )
    (comp (ref "U43")
      (value "REF35125QDBVR")
      (footprint "easyedapro:SOT-23-6_L2.9-W1.6-P0.95-LS2.8-BR")
      (description "输出类型:固定;输入电压:1.5V~6V;输出电压:1.25V;输出电流:10mA;精度:±0.05%;")
      (fields (field (name "Manufacturer") "TI(德州仪器)"))
      (libsource (lib "easyedapro") (part "REF35125QDBVR"))
    )
    (comp (ref "U44")
      (value "OPA320AIDBVR")
      (footprint "easyedapro:SOT-23-5_L3.0-W1.7-P0.95-LS2.8-BR")
      (description "放大器数:单路;增益带宽积(GBP):20MHz;输入偏置电流(Ib):0.2pA;压摆率(SR):10V/us;轨到轨:-;")
      (fields (field (name "Manufacturer") "TI(德州仪器)"))
      (libsource (lib "easyedapro") (part "OPA320AIDBVR"))
    )
    (comp (ref "C17")
      (value "100nF")
      (footprint "easyedapro:C0603")
      (description "容值:100nF;精度:±10%;额定电压:10V;材质(温度系数):X7R;")
      (fields
        (field (name "Manufacturer Part") "CC0603KRX7R6BB104")
        (field (name "Manufacturer") "YAGEO(国巨)")
      )
      (libsource (lib "easyedapro") (part "CC0603KRX7R6BB104"))
    )
    (comp (ref "C18")
      (value "100nF")
      (footprint "easyedapro:C0603")
      (description "容值:100nF;精度:±10%;额定电压:10V;材质(温度系数):X7R;")
      (fields
        (field (name "Manufacturer Part") "CC0603KRX7R6BB104")
        (field (name "Manufacturer") "YAGEO(国巨)")
      )
      (libsource (lib "easyedapro") (part "CC0603KRX7R6BB104"))
    )
    (comp (ref "C19")
      (value "100nF")
      (footprint "easyedapro:C0603")
      (description "容值:100nF;精度:±10%;额定电压:10V;材质(温度系数):X7R;")
      (fields
        (field (name "Manufacturer Part") "CC0603KRX7R6BB104")
        (field (name "Manufacturer") "YAGEO(国巨)")
      )
      (libsource (lib "easyedapro") (part "CC0603KRX7R6BB104"))
    )
    (comp (ref "C20")
      (value "100nF")
      (footprint "easyedapro:C0603")
      (description "容值:100nF;精度:±10%;额定电压:10V;材质(温度系数):X7R;")
      (fields
        (field (name "Manufacturer Part") "CC0603KRX7R6BB104")
        (field (name "Manufacturer") "YAGEO(国巨)")
      )
      (libsource (lib "easyedapro") (part "CC0603KRX7R6BB104"))
    )
    (comp (ref "C21")
      (value "100nF")
      (footprint "easyedapro:C0603")
      (description "容值:100nF;精度:±10%;额定电压:10V;材质(温度系数):X7R;")
      (fields
        (field (name "Manufacturer Part") "CC0603KRX7R6BB104")
        (field (name "Manufacturer") "YAGEO(国巨)")
      )
      (libsource (lib "easyedapro") (part "CC0603KRX7R6BB104"))
    )
    (comp (ref "C22")
      (value "100nF")
      (footprint "easyedapro:C0603")
      (description "容值:100nF;精度:±10%;额定电压:10V;材质(温度系数):X7R;")
      (fields
        (field (name "Manufacturer Part") "CC0603KRX7R6BB104")
        (field (name "Manufacturer") "YAGEO(国巨)")
      )
      (libsource (lib "easyedapro") (part "CC0603KRX7R6BB104"))
    )
    (comp (ref "C23")
      (value "100nF")
      (footprint "easyedapro:C0603")
      (description "容值:100nF;精度:±10%;额定电压:10V;材质(温度系数):X7R;")
      (fields
        (field (name "Manufacturer Part") "CC0603KRX7R6BB104")
        (field (name "Manufacturer") "YAGEO(国巨)")
      )
      (libsource (lib "easyedapro") (part "CC0603KRX7R6BB104"))
    )
    (comp (ref "C24")
      (value "100nF")
      (footprint "easyedapro:C0603")
      (description "容值:100nF;精度:±10%;额定电压:10V;材质(温度系数):X7R;")
      (fields
        (field (name "Manufacturer Part") "CC0603KRX7R6BB104")
        (field (name "Manufacturer") "YAGEO(国巨)")
      )
      (libsource (lib "easyedapro") (part "CC0603KRX7R6BB104"))
    )
    (comp (ref "C25")
      (value "100nF")
      (footprint "easyedapro:C0603")
      (description "容值:100nF;精度:±10%;额定电压:10V;材质(温度系数):X7R;")
      (fields
        (field (name "Manufacturer Part") "CC0603KRX7R6BB104")
        (field (name "Manufacturer") "YAGEO(国巨)")
      )
      (libsource (lib "easyedapro") (part "CC0603KRX7R6BB104"))
    )
    (comp (ref "C26")
      (value "100nF")
      (footprint "easyedapro:C0603")
      (description "容值:100nF;精度:±10%;额定电压:10V;材质(温度系数):X7R;")
      (fields
        (field (name "Manufacturer Part") "CC0603KRX7R6BB104")
        (field (name "Manufacturer") "YAGEO(国巨)")
      )
      (libsource (lib "easyedapro") (part "CC0603KRX7R6BB104"))
    )
    (comp (ref "C27")
      (value "100nF")
      (footprint "easyedapro:C0603")
      (description "容值:100nF;精度:±10%;额定电压:10V;材质(温度系数):X7R;")
      (fields
        (field (name "Manufacturer Part") "CC0603KRX7R6BB104")
        (field (name "Manufacturer") "YAGEO(国巨)")
      )
      (libsource (lib "easyedapro") (part "CC0603KRX7R6BB104"))
    )
    (comp (ref "C28")
      (value "100nF")
      (footprint "easyedapro:C0603")
      (description "容值:100nF;精度:±10%;额定电压:10V;材质(温度系数):X7R;")
      (fields
        (field (name "Manufacturer Part") "CC0603KRX7R6BB104")
        (field (name "Manufacturer") "YAGEO(国巨)")
      )
      (libsource (lib "easyedapro") (part "CC0603KRX7R6BB104"))
    )
    (comp (ref "C29")
      (value "100nF")
      (footprint "easyedapro:C0603")
      (description "容值:100nF;精度:±10%;额定电压:10V;材质(温度系数):X7R;")
      (fields
        (field (name "Manufacturer Part") "CC0603KRX7R6BB104")
        (field (name "Manufacturer") "YAGEO(国巨)")
      )
      (libsource (lib "easyedapro") (part "CC0603KRX7R6BB104"))
    )
    (comp (ref "C30")
      (value "100nF")
      (footprint "easyedapro:C0603")
      (description "容值:100nF;精度:±10%;额定电压:10V;材质(温度系数):X7R;")
      (fields
        (field (name "Manufacturer Part") "CC0603KRX7R6BB104")
        (field (name "Manufacturer") "YAGEO(国巨)")
      )
      (libsource (lib "easyedapro") (part "CC0603KRX7R6BB104"))
    )
    (comp (ref "C31")
      (value "100nF")
      (footprint "easyedapro:C0603")
      (description "容值:100nF;精度:±10%;额定电压:10V;材质(温度系数):X7R;")
      (fields
        (field (name "Manufacturer Part") "CC0603KRX7R6BB104")
        (field (name "Manufacturer") "YAGEO(国巨)")
      )
      (libsource (lib "easyedapro") (part "CC0603KRX7R6BB104"))
    )
    (comp (ref "C32")
      (value "100nF")
      (footprint "easyedapro:C0603")
      (description "容值:100nF;精度:±10%;额定电压:10V;材质(温度系数):X7R;")
      (fields
        (field (name "Manufacturer Part") "CC0603KRX7R6BB104")
        (field (name "Manufacturer") "YAGEO(国巨)")
      )
      (libsource (lib "easyedapro") (part "CC0603KRX7R6BB104"))
    )
    (comp (ref "R9")
      (value "160kΩ 0.1%")
      (footprint "easyedapro:R0603")
      (description "电阻类型:薄膜电阻;阻值:160kΩ;精度:±0.1%;功率:100mW;最大工作电压:75V;温度系数:±25ppm/°C;")
      (fields (field (name "Manufacturer Part") "ERA3AEB164V") (field (name "Manufacturer") "PANASONIC(松下)"))
      (libsource (lib "easyedapro") (part "ERA3AEB164V"))
    )
    (comp (ref "R10")
      (value "160kΩ 0.1%")
      (footprint "easyedapro:R0603")
      (description "电阻类型:薄膜电阻;阻值:160kΩ;精度:±0.1%;功率:100mW;最大工作电压:75V;温度系数:±25ppm/°C;")
      (fields (field (name "Manufacturer Part") "ERA3AEB164V") (field (name "Manufacturer") "PANASONIC(松下)"))
      (libsource (lib "easyedapro") (part "ERA3AEB164V"))
    )
    (comp (ref "R11")
      (value "160kΩ 0.1%")
      (footprint "easyedapro:R0603")
      (description "电阻类型:薄膜电阻;阻值:160kΩ;精度:±0.1%;功率:100mW;最大工作电压:75V;温度系数:±25ppm/°C;")
      (fields (field (name "Manufacturer Part") "ERA3AEB164V") (field (name "Manufacturer") "PANASONIC(松下)"))
      (libsource (lib "easyedapro") (part "ERA3AEB164V"))
    )
    (comp (ref "R12")
      (value "160kΩ 0.1%")
      (footprint "easyedapro:R0603")
      (description "电阻类型:薄膜电阻;阻值:160kΩ;精度:±0.1%;功率:100mW;最大工作电压:75V;温度系数:±25ppm/°C;")
      (fields (field (name "Manufacturer Part") "ERA3AEB164V") (field (name "Manufacturer") "PANASONIC(松下)"))
      (libsource (lib "easyedapro") (part "ERA3AEB164V"))
    )
    (comp (ref "R13")
      (value "160kΩ 0.1%")
      (footprint "easyedapro:R0603")
      (description "电阻类型:薄膜电阻;阻值:160kΩ;精度:±0.1%;功率:100mW;最大工作电压:75V;温度系数:±25ppm/°C;")
      (fields (field (name "Manufacturer Part") "ERA3AEB164V") (field (name "Manufacturer") "PANASONIC(松下)"))
      (libsource (lib "easyedapro") (part "ERA3AEB164V"))
    )
    (comp (ref "R14")
      (value "160kΩ 0.1%")
      (footprint "easyedapro:R0603")
      (description "电阻类型:薄膜电阻;阻值:160kΩ;精度:±0.1%;功率:100mW;最大工作电压:75V;温度系数:±25ppm/°C;")
      (fields (field (name "Manufacturer Part") "ERA3AEB164V") (field (name "Manufacturer") "PANASONIC(松下)"))
      (libsource (lib "easyedapro") (part "ERA3AEB164V"))
    )
    (comp (ref "R15")
      (value "160kΩ 0.1%")
      (footprint "easyedapro:R0603")
      (description "电阻类型:薄膜电阻;阻值:160kΩ;精度:±0.1%;功率:100mW;最大工作电压:75V;温度系数:±25ppm/°C;")
      (fields (field (name "Manufacturer Part") "ERA3AEB164V") (field (name "Manufacturer") "PANASONIC(松下)"))
      (libsource (lib "easyedapro") (part "ERA3AEB164V"))
    )
    (comp (ref "R16")
      (value "160kΩ 0.1%")
      (footprint "easyedapro:R0603")
      (description "电阻类型:薄膜电阻;阻值:160kΩ;精度:±0.1%;功率:100mW;最大工作电压:75V;温度系数:±25ppm/°C;")
      (fields (field (name "Manufacturer Part") "ERA3AEB164V") (field (name "Manufacturer") "PANASONIC(松下)"))
      (libsource (lib "easyedapro") (part "ERA3AEB164V"))
    )
    (comp (ref "R45") (value "NC") (footprint "easyedapro:R0603") (libsource (lib "easyedapro") (part "电阻")))
    (comp (ref "R46") (value "NC") (footprint "easyedapro:R0603") (libsource (lib "easyedapro") (part "电阻")))
    (comp (ref "R47") (value "NC") (footprint "easyedapro:R0603") (libsource (lib "easyedapro") (part "电阻")))
    (comp (ref "R48") (value "NC") (footprint "easyedapro:R0603") (libsource (lib "easyedapro") (part "电阻")))
    (comp (ref "R49") (value "NC") (footprint "easyedapro:R0603") (libsource (lib "easyedapro") (part "电阻")))
    (comp (ref "R50") (value "NC") (footprint "easyedapro:R0603") (libsource (lib "easyedapro") (part "电阻")))
    (comp (ref "R51") (value "NC") (footprint "easyedapro:R0603") (libsource (lib "easyedapro") (part "电阻")))
    (comp (ref "R52") (value "NC") (footprint "easyedapro:R0603") (libsource (lib "easyedapro") (part "电阻")))
    (comp (ref "U18")
      (value "INA333AIDGKR")
      (footprint "easyedapro:MSOP-8_L3.0-W3.0-P0.65-LS5.0-BL")
      (description "放大器数:单路;输入偏置电流(Ib):70pA;输入失调电压(Vos):10uV;压摆率(SR):0.16V/us;带宽(-3db):150kHz;轨到轨:-;")
      (fields (field (name "Manufacturer") "TI(德州仪器)"))
      (libsource (lib "easyedapro") (part "INA333AIDGKR"))
    )
    (comp (ref "U20")
      (value "INA333AIDGKR")
      (footprint "easyedapro:MSOP-8_L3.0-W3.0-P0.65-LS5.0-BL")
      (description "放大器数:单路;输入偏置电流(Ib):70pA;输入失调电压(Vos):10uV;压摆率(SR):0.16V/us;带宽(-3db):150kHz;轨到轨:-;")
      (fields (field (name "Manufacturer") "TI(德州仪器)"))
      (libsource (lib "easyedapro") (part "INA333AIDGKR"))
    )
    (comp (ref "U22")
      (value "INA333AIDGKR")
      (footprint "easyedapro:MSOP-8_L3.0-W3.0-P0.65-LS5.0-BL")
      (description "放大器数:单路;输入偏置电流(Ib):70pA;输入失调电压(Vos):10uV;压摆率(SR):0.16V/us;带宽(-3db):150kHz;轨到轨:-;")
      (fields (field (name "Manufacturer") "TI(德州仪器)"))
      (libsource (lib "easyedapro") (part "INA333AIDGKR"))
    )
    (comp (ref "U24")
      (value "INA333AIDGKR")
      (footprint "easyedapro:MSOP-8_L3.0-W3.0-P0.65-LS5.0-BL")
      (description "放大器数:单路;输入偏置电流(Ib):70pA;输入失调电压(Vos):10uV;压摆率(SR):0.16V/us;带宽(-3db):150kHz;轨到轨:-;")
      (fields (field (name "Manufacturer") "TI(德州仪器)"))
      (libsource (lib "easyedapro") (part "INA333AIDGKR"))
    )
    (comp (ref "U27")
      (value "INA333AIDGKR")
      (footprint "easyedapro:MSOP-8_L3.0-W3.0-P0.65-LS5.0-BL")
      (description "放大器数:单路;输入偏置电流(Ib):70pA;输入失调电压(Vos):10uV;压摆率(SR):0.16V/us;带宽(-3db):150kHz;轨到轨:-;")
      (fields (field (name "Manufacturer") "TI(德州仪器)"))
      (libsource (lib "easyedapro") (part "INA333AIDGKR"))
    )
    (comp (ref "U28")
      (value "INA333AIDGKR")
      (footprint "easyedapro:MSOP-8_L3.0-W3.0-P0.65-LS5.0-BL")
      (description "放大器数:单路;输入偏置电流(Ib):70pA;输入失调电压(Vos):10uV;压摆率(SR):0.16V/us;带宽(-3db):150kHz;轨到轨:-;")
      (fields (field (name "Manufacturer") "TI(德州仪器)"))
      (libsource (lib "easyedapro") (part "INA333AIDGKR"))
    )
    (comp (ref "U30")
      (value "INA333AIDGKR")
      (footprint "easyedapro:MSOP-8_L3.0-W3.0-P0.65-LS5.0-BL")
      (description "放大器数:单路;输入偏置电流(Ib):70pA;输入失调电压(Vos):10uV;压摆率(SR):0.16V/us;带宽(-3db):150kHz;轨到轨:-;")
      (fields (field (name "Manufacturer") "TI(德州仪器)"))
      (libsource (lib "easyedapro") (part "INA333AIDGKR"))
    )
    (comp (ref "U32")
      (value "INA333AIDGKR")
      (footprint "easyedapro:MSOP-8_L3.0-W3.0-P0.65-LS5.0-BL")
      (description "放大器数:单路;输入偏置电流(Ib):70pA;输入失调电压(Vos):10uV;压摆率(SR):0.16V/us;带宽(-3db):150kHz;轨到轨:-;")
      (fields (field (name "Manufacturer") "TI(德州仪器)"))
      (libsource (lib "easyedapro") (part "INA333AIDGKR"))
    )
    (comp (ref "U53")
      (value "CT100LW-HS6-M")
      (footprint "easyedapro:TSOT-23-6_L2.9-W1.6-P0.95-LS2.8-BL")
      (description "工作点(Gs):-;释放点(Gs):-;")
      (fields (field (name "Manufacturer") "muRata(村田)"))
      (libsource (lib "easyedapro") (part "CT100LW-HS6-M"))
    )
    (comp (ref "U54")
      (value "CT100LW-HS6-M")
      (footprint "easyedapro:TSOT-23-6_L2.9-W1.6-P0.95-LS2.8-BL")
      (description "工作点(Gs):-;释放点(Gs):-;")
      (fields (field (name "Manufacturer") "muRata(村田)"))
      (libsource (lib "easyedapro") (part "CT100LW-HS6-M"))
    )
    (comp (ref "U55")
      (value "CT100LW-HS6-M")
      (footprint "easyedapro:TSOT-23-6_L2.9-W1.6-P0.95-LS2.8-BL")
      (description "工作点(Gs):-;释放点(Gs):-;")
      (fields (field (name "Manufacturer") "muRata(村田)"))
      (libsource (lib "easyedapro") (part "CT100LW-HS6-M"))
    )
    (comp (ref "U56")
      (value "CT100LW-HS6-M")
      (footprint "easyedapro:TSOT-23-6_L2.9-W1.6-P0.95-LS2.8-BL")
      (description "工作点(Gs):-;释放点(Gs):-;")
      (fields (field (name "Manufacturer") "muRata(村田)"))
      (libsource (lib "easyedapro") (part "CT100LW-HS6-M"))
    )
    (comp (ref "U57")
      (value "CT100LW-HS6-M")
      (footprint "easyedapro:TSOT-23-6_L2.9-W1.6-P0.95-LS2.8-BL")
      (description "工作点(Gs):-;释放点(Gs):-;")
      (fields (field (name "Manufacturer") "muRata(村田)"))
      (libsource (lib "easyedapro") (part "CT100LW-HS6-M"))
    )
    (comp (ref "U58")
      (value "CT100LW-HS6-M")
      (footprint "easyedapro:TSOT-23-6_L2.9-W1.6-P0.95-LS2.8-BL")
      (description "工作点(Gs):-;释放点(Gs):-;")
      (fields (field (name "Manufacturer") "muRata(村田)"))
      (libsource (lib "easyedapro") (part "CT100LW-HS6-M"))
    )
    (comp (ref "U59")
      (value "CT100LW-HS6-M")
      (footprint "easyedapro:TSOT-23-6_L2.9-W1.6-P0.95-LS2.8-BL")
      (description "工作点(Gs):-;释放点(Gs):-;")
      (fields (field (name "Manufacturer") "muRata(村田)"))
      (libsource (lib "easyedapro") (part "CT100LW-HS6-M"))
    )
    (comp (ref "U60")
      (value "CT100LW-HS6-M")
      (footprint "easyedapro:TSOT-23-6_L2.9-W1.6-P0.95-LS2.8-BL")
      (description "工作点(Gs):-;释放点(Gs):-;")
      (fields (field (name "Manufacturer") "muRata(村田)"))
      (libsource (lib "easyedapro") (part "CT100LW-HS6-M"))
    )
  )
  (nets
    (net (code "1") (name "ADD") (class "Default")
      (node (ref "R1") (pin "2") (pinfunction "2_2") (pintype "unspecified"))
      (node (ref "R10") (pin "2") (pinfunction "2_2") (pintype "unspecified"))
      (node (ref "R11") (pin "2") (pinfunction "2_2") (pintype "unspecified"))
      (node (ref "R12") (pin "2") (pinfunction "2_2") (pintype "unspecified"))
      (node (ref "R13") (pin "2") (pinfunction "2_2") (pintype "unspecified"))
      (node (ref "R14") (pin "2") (pinfunction "2_2") (pintype "unspecified"))
      (node (ref "R15") (pin "2") (pinfunction "2_2") (pintype "unspecified"))
      (node (ref "R16") (pin "2") (pinfunction "2_2") (pintype "unspecified"))
      (node (ref "R2") (pin "2") (pinfunction "2_2") (pintype "unspecified"))
      (node (ref "R20") (pin "2") (pinfunction "2_2") (pintype "input"))
      (node (ref "R25") (pin "2") (pinfunction "2_2") (pintype "input"))
      (node (ref "R3") (pin "2") (pinfunction "2_2") (pintype "unspecified"))
      (node (ref "R4") (pin "2") (pinfunction "2_2") (pintype "unspecified"))
      (node (ref "R5") (pin "2") (pinfunction "2_2") (pintype "unspecified"))
      (node (ref "R6") (pin "2") (pinfunction "2_2") (pintype "unspecified"))
      (node (ref "R7") (pin "2") (pinfunction "2_2") (pintype "unspecified"))
      (node (ref "R8") (pin "2") (pinfunction "2_2") (pintype "unspecified"))
      (node (ref "R9") (pin "2") (pinfunction "2_2") (pintype "unspecified"))
    )
    (net (code "2") (name "ADD-1") (class "Default")
      (node (ref "R20") (pin "1") (pinfunction "1_1") (pintype "input"))
      (node (ref "U37") (pin "3") (pinfunction "IN+_3") (pintype "unspecified"))
    )
    (net (code "3") (name "ADD-2") (class "Default")
      (node (ref "R25") (pin "1") (pinfunction "1_1") (pintype "input"))
      (node (ref "U42") (pin "3") (pinfunction "IN+_3") (pintype "input"))
    )
    (net (code "4") (name "CNV") (class "Default")
      (node (ref "CN2") (pin "14") (pinfunction "14_14") (pintype "unspecified"))
      (node (ref "U34") (pin "6") (pinfunction "CNV_6") (pintype "unspecified"))
    )
    (net (code "5") (name "G1") (class "Default")
      (node (ref "C33") (pin "1") (pinfunction "1_1") (pintype "unspecified"))
      (node (ref "C34") (pin "1") (pinfunction "1_1") (pintype "unspecified"))
      (node (ref "C35") (pin "1") (pinfunction "1_1") (pintype "input"))
      (node (ref "C36") (pin "1") (pinfunction "1_1") (pintype "input"))
      (node (ref "C37") (pin "1") (pinfunction "1_1") (pintype "input"))
      (node (ref "C39") (pin "2") (pinfunction "2_2") (pintype "unspecified"))
      (node (ref "C40") (pin "1") (pinfunction "1_1") (pintype "input"))
      (node (ref "C41") (pin "1") (pinfunction "1_1") (pintype "input"))
      (node (ref "C42") (pin "1") (pinfunction "1_1") (pintype "input"))
      (node (ref "C43") (pin "1") (pinfunction "1_1") (pintype "unspecified"))
      (node (ref "C44") (pin "1") (pinfunction "1_1") (pintype "input"))
      (node (ref "C45") (pin "1") (pinfunction "1_1") (pintype "input"))
      (node (ref "C46") (pin "1") (pinfunction "1_1") (pintype "input"))
      (node (ref "C47") (pin "1") (pinfunction "1_1") (pintype "input"))
      (node (ref "C59") (pin "1") (pinfunction "1_1") (pintype "unspecified"))
      (node (ref "CN2") (pin "1") (pinfunction "1_1") (pintype "unspecified"))
      (node (ref "CN2") (pin "3") (pinfunction "3_3") (pintype "unspecified"))
      (node (ref "R23") (pin "1") (pinfunction "1_1") (pintype "input"))
      (node (ref "U33") (pin "1") (pinfunction "GND_1") (pintype "unspecified"))
      (node (ref "U33") (pin "2") (pinfunction "GND_2") (pintype "unspecified"))
      (node (ref "U34") (pin "4") (pinfunction "IN-_4") (pintype "unspecified"))
      (node (ref "U34") (pin "5") (pinfunction "GND_5") (pintype "unspecified"))
      (node (ref "U36") (pin "1") (pinfunction "GND_1") (pintype "unspecified"))
      (node (ref "U36") (pin "2") (pinfunction "GND_2") (pintype "unspecified"))
      (node (ref "U37") (pin "2") (pinfunction "V-_2") (pintype "unspecified"))
      (node (ref "U38") (pin "2") (pinfunction "GND_2") (pintype "input"))
      (node (ref "U39") (pin "2") (pinfunction "GND_2") (pintype "input"))
      (node (ref "U44") (pin "2") (pinfunction "V-_2") (pintype "unspecified"))
    )
    (net (code "6") (name "G2") (class "Default")
      (node (ref "C48") (pin "1") (pinfunction "1_1") (pintype "unspecified"))
      (node (ref "C49") (pin "2") (pinfunction "2_2") (pintype "input"))
      (node (ref "C50") (pin "2") (pinfunction "2_2") (pintype "input"))
      (node (ref "C51") (pin "2") (pinfunction "2_2") (pintype "input"))
      (node (ref "C52") (pin "1") (pinfunction "1_1") (pintype "unspecified"))
      (node (ref "C53") (pin "1") (pinfunction "1_1") (pintype "input"))
      (node (ref "C54") (pin "1") (pinfunction "1_1") (pintype "unspecified"))
      (node (ref "C55") (pin "1") (pinfunction "1_1") (pintype "input"))
      (node (ref "C56") (pin "1") (pinfunction "1_1") (pintype "input"))
      (node (ref "C57") (pin "1") (pinfunction "1_1") (pintype "unspecified"))
      (node (ref "C58") (pin "1") (pinfunction "1_1") (pintype "input"))
      (node (ref "H2") (pin "1") (pinfunction "1_1") (pintype "unspecified"))
      (node (ref "H3") (pin "2") (pinfunction "2_2") (pintype "unspecified"))
      (node (ref "R31") (pin "1") (pinfunction "1_1") (pintype "input"))
      (node (ref "U40") (pin "1") (pinfunction "GND_F_1") (pintype "unspecified"))
      (node (ref "U40") (pin "2") (pinfunction "GND_S_2") (pintype "unspecified"))
      (node (ref "U41") (pin "3") (pinfunction "IN+_3") (pintype "input"))
      (node (ref "U43") (pin "1") (pinfunction "GND_1") (pintype "unspecified"))
      (node (ref "U43") (pin "2") (pinfunction "GND_2") (pintype "unspecified"))
    )
    (net (code "7") (name "GND") (class "Default")
      (node (ref "C1") (pin "1") (pinfunction "1_1") (pintype "unspecified"))
      (node (ref "C10") (pin "2") (pinfunction "2_2") (pintype "unspecified"))
      (node (ref "C11") (pin "1") (pinfunction "1_1") (pintype "unspecified"))
      (node (ref "C12") (pin "2") (pinfunction "2_2") (pintype "unspecified"))
      (node (ref "C13") (pin "1") (pinfunction "1_1") (pintype "unspecified"))
      (node (ref "C14") (pin "2") (pinfunction "2_2") (pintype "unspecified"))
      (node (ref "C15") (pin "2") (pinfunction "2_2") (pintype "unspecified"))
      (node (ref "C16") (pin "1") (pinfunction "1_1") (pintype "unspecified"))
      (node (ref "C17") (pin "1") (pinfunction "1_1") (pintype "unspecified"))
      (node (ref "C18") (pin "2") (pinfunction "2_2") (pintype "unspecified"))
      (node (ref "C19") (pin "2") (pinfunction "2_2") (pintype "unspecified"))
      (node (ref "C2") (pin "2") (pinfunction "2_2") (pintype "unspecified"))
      (node (ref "C20") (pin "1") (pinfunction "1_1") (pintype "unspecified"))
      (node (ref "C21") (pin "1") (pinfunction "1_1") (pintype "unspecified"))
      (node (ref "C22") (pin "2") (pinfunction "2_2") (pintype "unspecified"))
      (node (ref "C23") (pin "2") (pinfunction "2_2") (pintype "unspecified"))
      (node (ref "C24") (pin "1") (pinfunction "1_1") (pintype "unspecified"))
      (node (ref "C25") (pin "1") (pinfunction "1_1") (pintype "unspecified"))
      (node (ref "C26") (pin "2") (pinfunction "2_2") (pintype "unspecified"))
      (node (ref "C27") (pin "1") (pinfunction "1_1") (pintype "unspecified"))
      (node (ref "C28") (pin "2") (pinfunction "2_2") (pintype "unspecified"))
      (node (ref "C29") (pin "1") (pinfunction "1_1") (pintype "unspecified"))
      (node (ref "C3") (pin "2") (pinfunction "2_2") (pintype "unspecified"))
      (node (ref "C30") (pin "2") (pinfunction "2_2") (pintype "unspecified"))
      (node (ref "C31") (pin "2") (pinfunction "2_2") (pintype "unspecified"))
      (node (ref "C32") (pin "1") (pinfunction "1_1") (pintype "unspecified"))
      (node (ref "C4") (pin "1") (pinfunction "1_1") (pintype "unspecified"))
      (node (ref "C5") (pin "1") (pinfunction "1_1") (pintype "unspecified"))
      (node (ref "C6") (pin "2") (pinfunction "2_2") (pintype "unspecified"))
      (node (ref "C7") (pin "2") (pinfunction "2_2") (pintype "unspecified"))
      (node (ref "C8") (pin "1") (pinfunction "1_1") (pintype "unspecified"))
      (node (ref "C9") (pin "1") (pinfunction "1_1") (pintype "unspecified"))
      (node (ref "R23") (pin "2") (pinfunction "2_2") (pintype "input"))
      (node (ref "R31") (pin "2") (pinfunction "2_2") (pintype "input"))
      (node (ref "U11") (pin "4") (pinfunction "V-_4") (pintype "unspecified"))
      (node (ref "U12") (pin "4") (pinfunction "V-_4") (pintype "unspecified"))
      (node (ref "U14") (pin "4") (pinfunction "V-_4") (pintype "unspecified"))
      (node (ref "U16") (pin "4") (pinfunction "V-_4") (pintype "unspecified"))
      (node (ref "U18") (pin "4") (pinfunction "V-_4") (pintype "unspecified"))
      (node (ref "U2") (pin "4") (pinfunction "V-_4") (pintype "unspecified"))
      (node (ref "U20") (pin "4") (pinfunction "V-_4") (pintype "unspecified"))
      (node (ref "U22") (pin "4") (pinfunction "V-_4") (pintype "unspecified"))
      (node (ref "U24") (pin "4") (pinfunction "V-_4") (pintype "unspecified"))
      (node (ref "U27") (pin "4") (pinfunction "V-_4") (pintype "unspecified"))
      (node (ref "U28") (pin "4") (pinfunction "V-_4") (pintype "unspecified"))
      (node (ref "U30") (pin "4") (pinfunction "V-_4") (pintype "unspecified"))
      (node (ref "U32") (pin "4") (pinfunction "V-_4") (pintype "unspecified"))
      (node (ref "U4") (pin "4") (pinfunction "V-_4") (pintype "unspecified"))
      (node (ref "U45") (pin "4") (pinfunction "GND_4") (pintype "unspecified"))
      (node (ref "U46") (pin "4") (pinfunction "GND_4") (pintype "unspecified"))
      (node (ref "U47") (pin "4") (pinfunction "GND_4") (pintype "unspecified"))
      (node (ref "U48") (pin "4") (pinfunction "GND_4") (pintype "unspecified"))
      (node (ref "U49") (pin "4") (pinfunction "GND_4") (pintype "unspecified"))
      (node (ref "U50") (pin "4") (pinfunction "GND_4") (pintype "unspecified"))
      (node (ref "U51") (pin "4") (pinfunction "GND_4") (pintype "unspecified"))
      (node (ref "U52") (pin "4") (pinfunction "GND_4") (pintype "unspecified"))
      (node (ref "U53") (pin "4") (pinfunction "GND_4") (pintype "unspecified"))
      (node (ref "U54") (pin "4") (pinfunction "GND_4") (pintype "unspecified"))
      (node (ref "U55") (pin "4") (pinfunction "GND_4") (pintype "unspecified"))
      (node (ref "U56") (pin "4") (pinfunction "GND_4") (pintype "unspecified"))
      (node (ref "U57") (pin "4") (pinfunction "GND_4") (pintype "unspecified"))
      (node (ref "U58") (pin "4") (pinfunction "GND_4") (pintype "unspecified"))
      (node (ref "U59") (pin "4") (pinfunction "GND_4") (pintype "unspecified"))
      (node (ref "U6") (pin "4") (pinfunction "V-_4") (pintype "unspecified"))
      (node (ref "U60") (pin "4") (pinfunction "GND_4") (pintype "unspecified"))
      (node (ref "U8") (pin "4") (pinfunction "V-_4") (pintype "unspecified"))
    )
    (net (code "8") (name "Net-(R37-Pad1)") (class "Default")
      (node (ref "R37") (pin "1") (pinfunction "1_1") (pintype "input"))
      (node (ref "U2") (pin "1") (pinfunction "RG_1") (pintype "unspecified"))
    )
    (net (code "9") (name "Net-(R37-Pad2)") (class "Default")
      (node (ref "R37") (pin "2") (pinfunction "2_2") (pintype "input"))
      (node (ref "U2") (pin "8") (pinfunction "RG_8") (pintype "unspecified"))
    )
    (net (code "10") (name "Net-(R38-Pad1)") (class "Default")
      (node (ref "R38") (pin "1") (pinfunction "1_1") (pintype "input"))
      (node (ref "U4") (pin "1") (pinfunction "RG_1") (pintype "unspecified"))
    )
    (net (code "11") (name "Net-(R38-Pad2)") (class "Default")
      (node (ref "R38") (pin "2") (pinfunction "2_2") (pintype "input"))
      (node (ref "U4") (pin "8") (pinfunction "RG_8") (pintype "unspecified"))
    )
    (net (code "12") (name "Net-(R39-Pad1)") (class "Default")
      (node (ref "R39") (pin "1") (pinfunction "1_1") (pintype "input"))
      (node (ref "U6") (pin "1") (pinfunction "RG_1") (pintype "unspecified"))
    )
    (net (code "13") (name "Net-(R39-Pad2)") (class "Default")
      (node (ref "R39") (pin "2") (pinfunction "2_2") (pintype "input"))
      (node (ref "U6") (pin "8") (pinfunction "RG_8") (pintype "unspecified"))
    )
    (net (code "14") (name "Net-(R40-Pad1)") (class "Default")
      (node (ref "R40") (pin "1") (pinfunction "1_1") (pintype "input"))
      (node (ref "U8") (pin "1") (pinfunction "RG_1") (pintype "unspecified"))
    )
    (net (code "15") (name "Net-(R40-Pad2)") (class "Default")
      (node (ref "R40") (pin "2") (pinfunction "2_2") (pintype "input"))
      (node (ref "U8") (pin "8") (pinfunction "RG_8") (pintype "unspecified"))
    )
    (net (code "16") (name "Net-(R41-Pad1)") (class "Default")
      (node (ref "R41") (pin "1") (pinfunction "1_1") (pintype "input"))
      (node (ref "U11") (pin "1") (pinfunction "RG_1") (pintype "unspecified"))
    )
    (net (code "17") (name "Net-(R41-Pad2)") (class "Default")
      (node (ref "R41") (pin "2") (pinfunction "2_2") (pintype "input"))
      (node (ref "U11") (pin "8") (pinfunction "RG_8") (pintype "unspecified"))
    )
    (net (code "18") (name "Net-(R42-Pad1)") (class "Default")
      (node (ref "R42") (pin "1") (pinfunction "1_1") (pintype "input"))
      (node (ref "U12") (pin "1") (pinfunction "RG_1") (pintype "unspecified"))
    )
    (net (code "19") (name "Net-(R42-Pad2)") (class "Default")
      (node (ref "R42") (pin "2") (pinfunction "2_2") (pintype "input"))
      (node (ref "U12") (pin "8") (pinfunction "RG_8") (pintype "unspecified"))
    )
    (net (code "20") (name "Net-(R43-Pad1)") (class "Default")
      (node (ref "R43") (pin "1") (pinfunction "1_1") (pintype "input"))
      (node (ref "U14") (pin "1") (pinfunction "RG_1") (pintype "unspecified"))
    )
    (net (code "21") (name "Net-(R43-Pad2)") (class "Default")
      (node (ref "R43") (pin "2") (pinfunction "2_2") (pintype "input"))
      (node (ref "U14") (pin "8") (pinfunction "RG_8") (pintype "unspecified"))
    )
    (net (code "22") (name "Net-(R44-Pad1)") (class "Default")
      (node (ref "R44") (pin "1") (pinfunction "1_1") (pintype "input"))
      (node (ref "U16") (pin "1") (pinfunction "RG_1") (pintype "unspecified"))
    )
    (net (code "23") (name "Net-(R44-Pad2)") (class "Default")
      (node (ref "R44") (pin "2") (pinfunction "2_2") (pintype "input"))
      (node (ref "U16") (pin "8") (pinfunction "RG_8") (pintype "unspecified"))
    )
    (net (code "24") (name "Net-(R45-Pad1)") (class "Default")
      (node (ref "R45") (pin "1") (pinfunction "1_1") (pintype "input"))
      (node (ref "U18") (pin "1") (pinfunction "RG_1") (pintype "unspecified"))
    )
    (net (code "25") (name "Net-(R45-Pad2)") (class "Default")
      (node (ref "R45") (pin "2") (pinfunction "2_2") (pintype "input"))
      (node (ref "U18") (pin "8") (pinfunction "RG_8") (pintype "unspecified"))
    )
    (net (code "26") (name "Net-(R46-Pad1)") (class "Default")
      (node (ref "R46") (pin "1") (pinfunction "1_1") (pintype "input"))
      (node (ref "U20") (pin "1") (pinfunction "RG_1") (pintype "unspecified"))
    )
    (net (code "27") (name "Net-(R46-Pad2)") (class "Default")
      (node (ref "R46") (pin "2") (pinfunction "2_2") (pintype "input"))
      (node (ref "U20") (pin "8") (pinfunction "RG_8") (pintype "unspecified"))
    )
    (net (code "28") (name "Net-(R47-Pad1)") (class "Default")
      (node (ref "R47") (pin "1") (pinfunction "1_1") (pintype "input"))
      (node (ref "U22") (pin "1") (pinfunction "RG_1") (pintype "unspecified"))
    )
    (net (code "29") (name "Net-(R47-Pad2)") (class "Default")
      (node (ref "R47") (pin "2") (pinfunction "2_2") (pintype "input"))
      (node (ref "U22") (pin "8") (pinfunction "RG_8") (pintype "unspecified"))
    )
    (net (code "30") (name "Net-(R48-Pad1)") (class "Default")
      (node (ref "R48") (pin "1") (pinfunction "1_1") (pintype "input"))
      (node (ref "U24") (pin "1") (pinfunction "RG_1") (pintype "unspecified"))
    )
    (net (code "31") (name "Net-(R48-Pad2)") (class "Default")
      (node (ref "R48") (pin "2") (pinfunction "2_2") (pintype "input"))
      (node (ref "U24") (pin "8") (pinfunction "RG_8") (pintype "unspecified"))
    )
    (net (code "32") (name "Net-(R49-Pad1)") (class "Default")
      (node (ref "R49") (pin "1") (pinfunction "1_1") (pintype "input"))
      (node (ref "U27") (pin "1") (pinfunction "RG_1") (pintype "unspecified"))
    )
    (net (code "33") (name "Net-(R49-Pad2)") (class "Default")
      (node (ref "R49") (pin "2") (pinfunction "2_2") (pintype "input"))
      (node (ref "U27") (pin "8") (pinfunction "RG_8") (pintype "unspecified"))
    )
    (net (code "34") (name "Net-(R50-Pad1)") (class "Default")
      (node (ref "R50") (pin "1") (pinfunction "1_1") (pintype "input"))
      (node (ref "U28") (pin "1") (pinfunction "RG_1") (pintype "unspecified"))
    )
    (net (code "35") (name "Net-(R50-Pad2)") (class "Default")
      (node (ref "R50") (pin "2") (pinfunction "2_2") (pintype "input"))
      (node (ref "U28") (pin "8") (pinfunction "RG_8") (pintype "unspecified"))
    )
    (net (code "36") (name "Net-(R51-Pad1)") (class "Default")
      (node (ref "R51") (pin "1") (pinfunction "1_1") (pintype "input"))
      (node (ref "U30") (pin "1") (pinfunction "RG_1") (pintype "unspecified"))
    )
    (net (code "37") (name "Net-(R51-Pad2)") (class "Default")
      (node (ref "R51") (pin "2") (pinfunction "2_2") (pintype "input"))
      (node (ref "U30") (pin "8") (pinfunction "RG_8") (pintype "unspecified"))
    )
    (net (code "38") (name "Net-(R52-Pad1)") (class "Default")
      (node (ref "R52") (pin "1") (pinfunction "1_1") (pintype "input"))
      (node (ref "U32") (pin "1") (pinfunction "RG_1") (pintype "unspecified"))
    )
    (net (code "39") (name "Net-(R52-Pad2)") (class "Default")
      (node (ref "R52") (pin "2") (pinfunction "2_2") (pintype "input"))
      (node (ref "U32") (pin "8") (pinfunction "RG_8") (pintype "unspecified"))
    )
    (net (code "40") (name "Net-(U2-VIN+)") (class "Default")
      (node (ref "U2") (pin "3") (pinfunction "VIN+_3") (pintype "unspecified"))
      (node (ref "U45") (pin "1") (pinfunction "X2_1") (pintype "unspecified"))
    )
    (net (code "41") (name "Net-(U2-VIN-)") (class "Default")
      (node (ref "U2") (pin "2") (pinfunction "VIN-_2") (pintype "unspecified"))
      (node (ref "U45") (pin "3") (pinfunction "X1_3") (pintype "unspecified"))
    )
    (net (code "42") (name "Net-(U2-VOUT)") (class "Default")
      (node (ref "R1") (pin "1") (pinfunction "1_1") (pintype "unspecified"))
      (node (ref "U2") (pin "6") (pinfunction "VOUT_6") (pintype "unspecified"))
    )
    (net (code "43") (name "Net-(U4-VIN+)") (class "Default")
      (node (ref "U4") (pin "3") (pinfunction "VIN+_3") (pintype "unspecified"))
      (node (ref "U46") (pin "1") (pinfunction "X2_1") (pintype "unspecified"))
    )
    (net (code "44") (name "Net-(U4-VIN-)") (class "Default")
      (node (ref "U4") (pin "2") (pinfunction "VIN-_2") (pintype "unspecified"))
      (node (ref "U46") (pin "3") (pinfunction "X1_3") (pintype "unspecified"))
    )
    (net (code "45") (name "Net-(U4-VOUT)") (class "Default")
      (node (ref "R2") (pin "1") (pinfunction "1_1") (pintype "unspecified"))
      (node (ref "U4") (pin "6") (pinfunction "VOUT_6") (pintype "unspecified"))
    )
    (net (code "46") (name "Net-(U6-VOUT)") (class "Default")
      (node (ref "R3") (pin "1") (pinfunction "1_1") (pintype "unspecified"))
      (node (ref "U6") (pin "6") (pinfunction "VOUT_6") (pintype "unspecified"))
    )
    (net (code "47") (name "Net-(U8-VOUT)") (class "Default")
      (node (ref "R4") (pin "1") (pinfunction "1_1") (pintype "unspecified"))
      (node (ref "U8") (pin "6") (pinfunction "VOUT_6") (pintype "unspecified"))
    )
    (net (code "48") (name "Net-(U11-VIN+)") (class "Default")
      (node (ref "U11") (pin "3") (pinfunction "VIN+_3") (pintype "unspecified"))
      (node (ref "U49") (pin "1") (pinfunction "X2_1") (pintype "unspecified"))
    )
    (net (code "49") (name "Net-(U11-VIN-)") (class "Default")
      (node (ref "U11") (pin "2") (pinfunction "VIN-_2") (pintype "unspecified"))
      (node (ref "U49") (pin "3") (pinfunction "X1_3") (pintype "unspecified"))
    )
    (net (code "50") (name "Net-(U11-VOUT)") (class "Default")
      (node (ref "R5") (pin "1") (pinfunction "1_1") (pintype "unspecified"))
      (node (ref "U11") (pin "6") (pinfunction "VOUT_6") (pintype "unspecified"))
    )
    (net (code "51") (name "Net-(U12-VIN+)") (class "Default")
      (node (ref "U12") (pin "3") (pinfunction "VIN+_3") (pintype "unspecified"))
      (node (ref "U50") (pin "1") (pinfunction "X2_1") (pintype "unspecified"))
    )
    (net (code "52") (name "Net-(U12-VIN-)") (class "Default")
      (node (ref "U12") (pin "2") (pinfunction "VIN-_2") (pintype "unspecified"))
      (node (ref "U50") (pin "3") (pinfunction "X1_3") (pintype "unspecified"))
    )
    (net (code "53") (name "Net-(U12-VOUT)") (class "Default")
      (node (ref "R6") (pin "1") (pinfunction "1_1") (pintype "unspecified"))
      (node (ref "U12") (pin "6") (pinfunction "VOUT_6") (pintype "unspecified"))
    )
    (net (code "54") (name "Net-(U14-VIN+)") (class "Default")
      (node (ref "U14") (pin "3") (pinfunction "VIN+_3") (pintype "unspecified"))
      (node (ref "U51") (pin "1") (pinfunction "X2_1") (pintype "unspecified"))
    )
    (net (code "55") (name "Net-(U14-VIN-)") (class "Default")
      (node (ref "U14") (pin "2") (pinfunction "VIN-_2") (pintype "unspecified"))
      (node (ref "U51") (pin "3") (pinfunction "X1_3") (pintype "unspecified"))
    )
    (net (code "56") (name "Net-(U14-VOUT)") (class "Default")
      (node (ref "R7") (pin "1") (pinfunction "1_1") (pintype "unspecified"))
      (node (ref "U14") (pin "6") (pinfunction "VOUT_6") (pintype "unspecified"))
    )
    (net (code "57") (name "Net-(U16-VIN+)") (class "Default")
      (node (ref "U16") (pin "3") (pinfunction "VIN+_3") (pintype "unspecified"))
      (node (ref "U52") (pin "1") (pinfunction "X2_1") (pintype "unspecified"))
    )
    (net (code "58") (name "Net-(U16-VIN-)") (class "Default")
      (node (ref "U16") (pin "2") (pinfunction "VIN-_2") (pintype "unspecified"))
      (node (ref "U52") (pin "3") (pinfunction "X1_3") (pintype "unspecified"))
    )
    (net (code "59") (name "Net-(U16-VOUT)") (class "Default")
      (node (ref "R8") (pin "1") (pinfunction "1_1") (pintype "unspecified"))
      (node (ref "U16") (pin "6") (pinfunction "VOUT_6") (pintype "unspecified"))
    )
    (net (code "60") (name "Net-(U18-VIN+)") (class "Default")
      (node (ref "U18") (pin "3") (pinfunction "VIN+_3") (pintype "unspecified"))
      (node (ref "U53") (pin "1") (pinfunction "X2_1") (pintype "unspecified"))
    )
    (net (code "61") (name "Net-(U18-VIN-)") (class "Default")
      (node (ref "U18") (pin "2") (pinfunction "VIN-_2") (pintype "unspecified"))
      (node (ref "U53") (pin "3") (pinfunction "X1_3") (pintype "unspecified"))
    )
    (net (code "62") (name "Net-(U18-VOUT)") (class "Default")
      (node (ref "R9") (pin "1") (pinfunction "1_1") (pintype "unspecified"))
      (node (ref "U18") (pin "6") (pinfunction "VOUT_6") (pintype "unspecified"))
    )
    (net (code "63") (name "Net-(U20-VIN+)") (class "Default")
      (node (ref "U20") (pin "3") (pinfunction "VIN+_3") (pintype "unspecified"))
      (node (ref "U54") (pin "1") (pinfunction "X2_1") (pintype "unspecified"))
    )
    (net (code "64") (name "Net-(U20-VIN-)") (class "Default")
      (node (ref "U20") (pin "2") (pinfunction "VIN-_2") (pintype "unspecified"))
      (node (ref "U54") (pin "3") (pinfunction "X1_3") (pintype "unspecified"))
    )
    (net (code "65") (name "Net-(U20-VOUT)") (class "Default")
      (node (ref "R10") (pin "1") (pinfunction "1_1") (pintype "unspecified"))
      (node (ref "U20") (pin "6") (pinfunction "VOUT_6") (pintype "unspecified"))
    )
    (net (code "66") (name "Net-(U22-VIN+)") (class "Default")
      (node (ref "U22") (pin "3") (pinfunction "VIN+_3") (pintype "unspecified"))
      (node (ref "U55") (pin "1") (pinfunction "X2_1") (pintype "unspecified"))
    )
    (net (code "67") (name "Net-(U22-VIN-)") (class "Default")
      (node (ref "U22") (pin "2") (pinfunction "VIN-_2") (pintype "unspecified"))
      (node (ref "U55") (pin "3") (pinfunction "X1_3") (pintype "unspecified"))
    )
    (net (code "68") (name "Net-(U22-VOUT)") (class "Default")
      (node (ref "R11") (pin "1") (pinfunction "1_1") (pintype "unspecified"))
      (node (ref "U22") (pin "6") (pinfunction "VOUT_6") (pintype "unspecified"))
    )
    (net (code "69") (name "Net-(U24-VIN+)") (class "Default")
      (node (ref "U24") (pin "3") (pinfunction "VIN+_3") (pintype "unspecified"))
      (node (ref "U56") (pin "1") (pinfunction "X2_1") (pintype "unspecified"))
    )
    (net (code "70") (name "Net-(U24-VIN-)") (class "Default")
      (node (ref "U24") (pin "2") (pinfunction "VIN-_2") (pintype "unspecified"))
      (node (ref "U56") (pin "3") (pinfunction "X1_3") (pintype "unspecified"))
    )
    (net (code "71") (name "Net-(U24-VOUT)") (class "Default")
      (node (ref "R12") (pin "1") (pinfunction "1_1") (pintype "unspecified"))
      (node (ref "U24") (pin "6") (pinfunction "VOUT_6") (pintype "unspecified"))
    )
    (net (code "72") (name "Net-(U27-VIN+)") (class "Default")
      (node (ref "U27") (pin "3") (pinfunction "VIN+_3") (pintype "unspecified"))
      (node (ref "U57") (pin "1") (pinfunction "X2_1") (pintype "unspecified"))
    )
    (net (code "73") (name "Net-(U27-VIN-)") (class "Default")
      (node (ref "U27") (pin "2") (pinfunction "VIN-_2") (pintype "unspecified"))
      (node (ref "U57") (pin "3") (pinfunction "X1_3") (pintype "unspecified"))
    )
    (net (code "74") (name "Net-(U27-VOUT)") (class "Default")
      (node (ref "R13") (pin "1") (pinfunction "1_1") (pintype "unspecified"))
      (node (ref "U27") (pin "6") (pinfunction "VOUT_6") (pintype "unspecified"))
    )
    (net (code "75") (name "Net-(U28-VIN+)") (class "Default")
      (node (ref "U28") (pin "3") (pinfunction "VIN+_3") (pintype "unspecified"))
      (node (ref "U58") (pin "1") (pinfunction "X2_1") (pintype "unspecified"))
    )
    (net (code "76") (name "Net-(U28-VIN-)") (class "Default")
      (node (ref "U28") (pin "2") (pinfunction "VIN-_2") (pintype "unspecified"))
      (node (ref "U58") (pin "3") (pinfunction "X1_3") (pintype "unspecified"))
    )
    (net (code "77") (name "Net-(U28-VOUT)") (class "Default")
      (node (ref "R14") (pin "1") (pinfunction "1_1") (pintype "unspecified"))
      (node (ref "U28") (pin "6") (pinfunction "VOUT_6") (pintype "unspecified"))
    )
    (net (code "78") (name "Net-(U30-VIN+)") (class "Default")
      (node (ref "U30") (pin "3") (pinfunction "VIN+_3") (pintype "unspecified"))
      (node (ref "U59") (pin "1") (pinfunction "X2_1") (pintype "unspecified"))
    )
    (net (code "79") (name "Net-(U30-VIN-)") (class "Default")
      (node (ref "U30") (pin "2") (pinfunction "VIN-_2") (pintype "unspecified"))
      (node (ref "U59") (pin "3") (pinfunction "X1_3") (pintype "unspecified"))
    )
    (net (code "80") (name "Net-(U30-VOUT)") (class "Default")
      (node (ref "R15") (pin "1") (pinfunction "1_1") (pintype "unspecified"))
      (node (ref "U30") (pin "6") (pinfunction "VOUT_6") (pintype "unspecified"))
    )
    (net (code "81") (name "Net-(U32-VIN+)") (class "Default")
      (node (ref "U32") (pin "3") (pinfunction "VIN+_3") (pintype "unspecified"))
      (node (ref "U60") (pin "1") (pinfunction "X2_1") (pintype "unspecified"))
    )
    (net (code "82") (name "Net-(U32-VIN-)") (class "Default")
      (node (ref "U32") (pin "2") (pinfunction "VIN-_2") (pintype "unspecified"))
      (node (ref "U60") (pin "3") (pinfunction "X1_3") (pintype "unspecified"))
    )
    (net (code "83") (name "Net-(U32-VOUT)") (class "Default")
      (node (ref "R16") (pin "1") (pinfunction "1_1") (pintype "unspecified"))
      (node (ref "U32") (pin "6") (pinfunction "VOUT_6") (pintype "unspecified"))
    )
    (net (code "84") (name "Net-(U33-NR)") (class "Default")
      (node (ref "C36") (pin "2") (pinfunction "2_2") (pintype "input"))
      (node (ref "U33") (pin "5") (pinfunction "NR_5") (pintype "unspecified"))
    )
    (net (code "85") (name "Net-(U34-IN+)") (class "Default")
      (node (ref "C43") (pin "2") (pinfunction "2_2") (pintype "unspecified"))
      (node (ref "R19") (pin "2") (pinfunction "2_2") (pintype "input"))
      (node (ref "U34") (pin "3") (pinfunction "IN+_3") (pintype "unspecified"))
    )
    (net (code "86") (name "Net-(U36-NR)") (class "Default")
      (node (ref "C41") (pin "2") (pinfunction "2_2") (pintype "input"))
      (node (ref "U36") (pin "5") (pinfunction "NR_5") (pintype "unspecified"))
    )
    (net (code "87") (name "Net-(U37-IN-)") (class "Default")
      (node (ref "C38") (pin "1") (pinfunction "1_1") (pintype "input"))
      (node (ref "R17") (pin "1") (pinfunction "1_1") (pintype "unspecified"))
      (node (ref "R18") (pin "2") (pinfunction "2_2") (pintype "input"))
      (node (ref "U37") (pin "4") (pinfunction "IN-_4") (pintype "unspecified"))
    )
    (net (code "88") (name "Net-(U37-OUT)") (class "Default")
      (node (ref "C38") (pin "2") (pinfunction "2_2") (pintype "input"))
      (node (ref "R17") (pin "2") (pinfunction "2_2") (pintype "unspecified"))
      (node (ref "U37") (pin "1") (pinfunction "OUT_1") (pintype "output"))
      (node (ref "U44") (pin "3") (pinfunction "IN+_3") (pintype "unspecified"))
    )
    (net (code "89") (name "Net-(U41-IN-)") (class "Default")
      (node (ref "R35") (pin "2") (pinfunction "2_2") (pintype "unspecified"))
      (node (ref "R36") (pin "1") (pinfunction "1_1") (pintype "input"))
      (node (ref "U41") (pin "4") (pinfunction "IN-_4") (pintype "input"))
    )
    (net (code "90") (name "Net-(U41-OUT)") (class "Default")
      (node (ref "H2") (pin "2") (pinfunction "2_2") (pintype "unspecified"))
      (node (ref "R36") (pin "2") (pinfunction "2_2") (pintype "input"))
      (node (ref "U41") (pin "1") (pinfunction "OUT_1") (pintype "input"))
    )
    (net (code "91") (name "Net-(U42-IN-)") (class "Default")
      (node (ref "C60") (pin "1") (pinfunction "1_1") (pintype "input"))
      (node (ref "R27") (pin "2") (pinfunction "2_2") (pintype "unspecified"))
      (node (ref "R28") (pin "1") (pinfunction "1_1") (pintype "unspecified"))
      (node (ref "U42") (pin "4") (pinfunction "IN-_4") (pintype "input"))
    )
    (net (code "92") (name "Net-(U42-OUT)") (class "Default")
      (node (ref "C60") (pin "2") (pinfunction "2_2") (pintype "input"))
      (node (ref "R28") (pin "2") (pinfunction "2_2") (pintype "unspecified"))
      (node (ref "R35") (pin "1") (pinfunction "1_1") (pintype "unspecified"))
      (node (ref "U42") (pin "1") (pinfunction "OUT_1") (pintype "input"))
    )
    (net (code "93") (name "Net-(U43-NR)") (class "Default")
      (node (ref "C55") (pin "2") (pinfunction "2_2") (pintype "input"))
      (node (ref "U43") (pin "5") (pinfunction "NR_5") (pintype "unspecified"))
    )
    (net (code "94") (name "Net-(U44-IN-)") (class "Default")
      (node (ref "R19") (pin "1") (pinfunction "1_1") (pintype "input"))
      (node (ref "U44") (pin "1") (pinfunction "OUT_1") (pintype "output"))
      (node (ref "U44") (pin "4") (pinfunction "IN-_4") (pintype "unspecified"))
    )
    (net (code "95") (name "Net-(U47-X1)") (class "Default")
      (node (ref "U47") (pin "3") (pinfunction "X1_3") (pintype "unspecified"))
      (node (ref "U6") (pin "2") (pinfunction "VIN-_2") (pintype "unspecified"))
    )
    (net (code "96") (name "Net-(U47-X2)") (class "Default")
      (node (ref "U47") (pin "1") (pinfunction "X2_1") (pintype "unspecified"))
      (node (ref "U6") (pin "3") (pinfunction "VIN+_3") (pintype "unspecified"))
    )
    (net (code "97") (name "Net-(U48-X1)") (class "Default")
      (node (ref "U48") (pin "3") (pinfunction "X1_3") (pintype "unspecified"))
      (node (ref "U8") (pin "2") (pinfunction "VIN-_2") (pintype "unspecified"))
    )
    (net (code "98") (name "Net-(U48-X2)") (class "Default")
      (node (ref "U48") (pin "1") (pinfunction "X2_1") (pintype "unspecified"))
      (node (ref "U8") (pin "3") (pinfunction "VIN+_3") (pintype "unspecified"))
    )
    (net (code "99") (name "SCK") (class "Default")
      (node (ref "CN2") (pin "18") (pinfunction "18_18") (pintype "unspecified"))
      (node (ref "U34") (pin "8") (pinfunction "SCK_8") (pintype "unspecified"))
    )
    (net (code "100") (name "SDI") (class "Default")
      (node (ref "CN2") (pin "20") (pinfunction "20_20") (pintype "unspecified"))
      (node (ref "U34") (pin "9") (pinfunction "SDI_9") (pintype "unspecified"))
    )
    (net (code "101") (name "SDO") (class "Default")
      (node (ref "CN2") (pin "16") (pinfunction "16_16") (pintype "unspecified"))
      (node (ref "U34") (pin "7") (pinfunction "SDO_7") (pintype "unspecified"))
    )
    (net (code "102") (name "V1.8_AD") (class "Default")
      (node (ref "C34") (pin "2") (pinfunction "2_2") (pintype "unspecified"))
      (node (ref "C47") (pin "2") (pinfunction "2_2") (pintype "input"))
      (node (ref "U34") (pin "10") (pinfunction "VIO_10") (pintype "unspecified"))
      (node (ref "U39") (pin "5") (pinfunction "OUT_5") (pintype "input"))
    )
    (net (code "103") (name "V1.25") (class "Default")
      (node (ref "R21") (pin "2") (pinfunction "2_2") (pintype "input"))
      (node (ref "R26") (pin "2") (pinfunction "2_2") (pintype "input"))
      (node (ref "U11") (pin "5") (pinfunction "REF_5") (pintype "unspecified"))
      (node (ref "U12") (pin "5") (pinfunction "REF_5") (pintype "unspecified"))
      (node (ref "U14") (pin "5") (pinfunction "REF_5") (pintype "unspecified"))
      (node (ref "U16") (pin "5") (pinfunction "REF_5") (pintype "unspecified"))
      (node (ref "U18") (pin "5") (pinfunction "REF_5") (pintype "unspecified"))
      (node (ref "U2") (pin "5") (pinfunction "REF_5") (pintype "unspecified"))
      (node (ref "U20") (pin "5") (pinfunction "REF_5") (pintype "unspecified"))
      (node (ref "U22") (pin "5") (pinfunction "REF_5") (pintype "unspecified"))
      (node (ref "U24") (pin "5") (pinfunction "REF_5") (pintype "unspecified"))
      (node (ref "U27") (pin "5") (pinfunction "REF_5") (pintype "unspecified"))
      (node (ref "U28") (pin "5") (pinfunction "REF_5") (pintype "unspecified"))
      (node (ref "U30") (pin "5") (pinfunction "REF_5") (pintype "unspecified"))
      (node (ref "U32") (pin "5") (pinfunction "REF_5") (pintype "unspecified"))
      (node (ref "U4") (pin "5") (pinfunction "REF_5") (pintype "unspecified"))
      (node (ref "U6") (pin "5") (pinfunction "REF_5") (pintype "unspecified"))
      (node (ref "U8") (pin "5") (pinfunction "REF_5") (pintype "unspecified"))
    )
    (net (code "104") (name "V1.25-TMR1") (class "Default")
      (node (ref "C42") (pin "2") (pinfunction "2_2") (pintype "input"))
      (node (ref "R18") (pin "1") (pinfunction "1_1") (pintype "input"))
      (node (ref "R21") (pin "1") (pinfunction "1_1") (pintype "input"))
      (node (ref "U36") (pin "6") (pinfunction "VREF_6") (pintype "unspecified"))
    )
    (net (code "105") (name "V1.25-TMR2") (class "Default")
      (node (ref "C56") (pin "2") (pinfunction "2_2") (pintype "input"))
      (node (ref "R26") (pin "1") (pinfunction "1_1") (pintype "input"))
      (node (ref "U43") (pin "6") (pinfunction "VREF_6") (pintype "unspecified"))
    )
    (net (code "106") (name "V2.5") (class "Default")
      (node (ref "C1") (pin "2") (pinfunction "2_2") (pintype "unspecified"))
      (node (ref "C11") (pin "2") (pinfunction "2_2") (pintype "unspecified"))
      (node (ref "C13") (pin "2") (pinfunction "2_2") (pintype "unspecified"))
      (node (ref "C16") (pin "2") (pinfunction "2_2") (pintype "unspecified"))
      (node (ref "C17") (pin "2") (pinfunction "2_2") (pintype "unspecified"))
      (node (ref "C20") (pin "2") (pinfunction "2_2") (pintype "unspecified"))
      (node (ref "C21") (pin "2") (pinfunction "2_2") (pintype "unspecified"))
      (node (ref "C24") (pin "2") (pinfunction "2_2") (pintype "unspecified"))
      (node (ref "C25") (pin "2") (pinfunction "2_2") (pintype "unspecified"))
      (node (ref "C27") (pin "2") (pinfunction "2_2") (pintype "unspecified"))
      (node (ref "C29") (pin "2") (pinfunction "2_2") (pintype "unspecified"))
      (node (ref "C32") (pin "2") (pinfunction "2_2") (pintype "unspecified"))
      (node (ref "C4") (pin "2") (pinfunction "2_2") (pintype "unspecified"))
      (node (ref "C5") (pin "2") (pinfunction "2_2") (pintype "unspecified"))
      (node (ref "C8") (pin "2") (pinfunction "2_2") (pintype "unspecified"))
      (node (ref "C9") (pin "2") (pinfunction "2_2") (pintype "unspecified"))
      (node (ref "R24") (pin "2") (pinfunction "2_2") (pintype "input"))
      (node (ref "R33") (pin "2") (pinfunction "2_2") (pintype "input"))
      (node (ref "U45") (pin "6") (pinfunction "VDD_6") (pintype "unspecified"))
      (node (ref "U46") (pin "6") (pinfunction "VDD_6") (pintype "unspecified"))
      (node (ref "U47") (pin "6") (pinfunction "VDD_6") (pintype "unspecified"))
      (node (ref "U48") (pin "6") (pinfunction "VDD_6") (pintype "unspecified"))
      (node (ref "U49") (pin "6") (pinfunction "VDD_6") (pintype "unspecified"))
      (node (ref "U50") (pin "6") (pinfunction "VDD_6") (pintype "unspecified"))
      (node (ref "U51") (pin "6") (pinfunction "VDD_6") (pintype "unspecified"))
      (node (ref "U52") (pin "6") (pinfunction "VDD_6") (pintype "unspecified"))
      (node (ref "U53") (pin "6") (pinfunction "VDD_6") (pintype "unspecified"))
      (node (ref "U54") (pin "6") (pinfunction "VDD_6") (pintype "unspecified"))
      (node (ref "U55") (pin "6") (pinfunction "VDD_6") (pintype "unspecified"))
      (node (ref "U56") (pin "6") (pinfunction "VDD_6") (pintype "unspecified"))
      (node (ref "U57") (pin "6") (pinfunction "VDD_6") (pintype "unspecified"))
      (node (ref "U58") (pin "6") (pinfunction "VDD_6") (pintype "unspecified"))
      (node (ref "U59") (pin "6") (pinfunction "VDD_6") (pintype "unspecified"))
      (node (ref "U60") (pin "6") (pinfunction "VDD_6") (pintype "unspecified"))
    )
    (net (code "107") (name "V2.5-TMR1") (class "Default")
      (node (ref "C37") (pin "2") (pinfunction "2_2") (pintype "input"))
      (node (ref "R24") (pin "1") (pinfunction "1_1") (pintype "input"))
      (node (ref "U33") (pin "6") (pinfunction "VREF_6") (pintype "unspecified"))
      (node (ref "U34") (pin "1") (pinfunction "REF_1") (pintype "unspecified"))
    )
    (net (code "108") (name "V2.5_AD") (class "Default")
      (node (ref "C39") (pin "1") (pinfunction "1_1") (pintype "unspecified"))
      (node (ref "C45") (pin "2") (pinfunction "2_2") (pintype "input"))
      (node (ref "U34") (pin "2") (pinfunction "VDD_2") (pintype "unspecified"))
      (node (ref "U38") (pin "5") (pinfunction "OUT_5") (pintype "input"))
    )
    (net (code "109") (name "V2.5_TMR2") (class "Default")
      (node (ref "C51") (pin "1") (pinfunction "1_1") (pintype "input"))
      (node (ref "C58") (pin "2") (pinfunction "2_2") (pintype "input"))
      (node (ref "R27") (pin "1") (pinfunction "1_1") (pintype "unspecified"))
      (node (ref "R32") (pin "1") (pinfunction "1_1") (pintype "input"))
      (node (ref "R33") (pin "1") (pinfunction "1_1") (pintype "input"))
      (node (ref "U40") (pin "5") (pinfunction "OUT_S_5") (pintype "unspecified"))
      (node (ref "U40") (pin "6") (pinfunction "OUT_F_6") (pintype "unspecified"))
      (node (ref "U43") (pin "3") (pinfunction "EN_3") (pintype "unspecified"))
      (node (ref "U43") (pin "4") (pinfunction "VIN_4") (pintype "unspecified"))
    )
    (net (code "110") (name "V3.3") (class "Default")
      (node (ref "C33") (pin "2") (pinfunction "2_2") (pintype "unspecified"))
      (node (ref "C35") (pin "2") (pinfunction "2_2") (pintype "input"))
      (node (ref "C40") (pin "2") (pinfunction "2_2") (pintype "input"))
      (node (ref "C44") (pin "2") (pinfunction "2_2") (pintype "input"))
      (node (ref "C46") (pin "2") (pinfunction "2_2") (pintype "input"))
      (node (ref "C59") (pin "2") (pinfunction "2_2") (pintype "unspecified"))
      (node (ref "CN2") (pin "2") (pinfunction "2_2") (pintype "unspecified"))
      (node (ref "CN2") (pin "4") (pinfunction "4_4") (pintype "unspecified"))
      (node (ref "R22") (pin "1") (pinfunction "1_1") (pintype "input"))
      (node (ref "U33") (pin "3") (pinfunction "EN_3") (pintype "unspecified"))
      (node (ref "U33") (pin "4") (pinfunction "VIN_4") (pintype "unspecified"))
      (node (ref "U36") (pin "3") (pinfunction "EN_3") (pintype "unspecified"))
      (node (ref "U36") (pin "4") (pinfunction "VIN_4") (pintype "unspecified"))
      (node (ref "U37") (pin "5") (pinfunction "V+_5") (pintype "unspecified"))
      (node (ref "U38") (pin "1") (pinfunction "IN_1") (pintype "input"))
      (node (ref "U38") (pin "3") (pinfunction "EN_3") (pintype "input"))
      (node (ref "U39") (pin "1") (pinfunction "IN_1") (pintype "input"))
      (node (ref "U39") (pin "3") (pinfunction "EN_3") (pintype "input"))
      (node (ref "U44") (pin "5") (pinfunction "V+_5") (pintype "unspecified"))
    )
    (net (code "111") (name "V3.3_INA") (class "Default")
      (node (ref "C10") (pin "1") (pinfunction "1_1") (pintype "unspecified"))
      (node (ref "C12") (pin "1") (pinfunction "1_1") (pintype "unspecified"))
      (node (ref "C14") (pin "1") (pinfunction "1_1") (pintype "unspecified"))
      (node (ref "C15") (pin "1") (pinfunction "1_1") (pintype "unspecified"))
      (node (ref "C18") (pin "1") (pinfunction "1_1") (pintype "unspecified"))
      (node (ref "C19") (pin "1") (pinfunction "1_1") (pintype "unspecified"))
      (node (ref "C2") (pin "1") (pinfunction "1_1") (pintype "unspecified"))
      (node (ref "C22") (pin "1") (pinfunction "1_1") (pintype "unspecified"))
      (node (ref "C23") (pin "1") (pinfunction "1_1") (pintype "unspecified"))
      (node (ref "C26") (pin "1") (pinfunction "1_1") (pintype "unspecified"))
      (node (ref "C28") (pin "1") (pinfunction "1_1") (pintype "unspecified"))
      (node (ref "C3") (pin "1") (pinfunction "1_1") (pintype "unspecified"))
      (node (ref "C30") (pin "1") (pinfunction "1_1") (pintype "unspecified"))
      (node (ref "C31") (pin "1") (pinfunction "1_1") (pintype "unspecified"))
      (node (ref "C6") (pin "1") (pinfunction "1_1") (pintype "unspecified"))
      (node (ref "C7") (pin "1") (pinfunction "1_1") (pintype "unspecified"))
      (node (ref "R22") (pin "2") (pinfunction "2_2") (pintype "input"))
      (node (ref "R32") (pin "2") (pinfunction "2_2") (pintype "input"))
      (node (ref "U11") (pin "7") (pinfunction "V+_7") (pintype "unspecified"))
      (node (ref "U12") (pin "7") (pinfunction "V+_7") (pintype "unspecified"))
      (node (ref "U14") (pin "7") (pinfunction "V+_7") (pintype "unspecified"))
      (node (ref "U16") (pin "7") (pinfunction "V+_7") (pintype "unspecified"))
      (node (ref "U18") (pin "7") (pinfunction "V+_7") (pintype "unspecified"))
      (node (ref "U2") (pin "7") (pinfunction "V+_7") (pintype "unspecified"))
      (node (ref "U20") (pin "7") (pinfunction "V+_7") (pintype "unspecified"))
      (node (ref "U22") (pin "7") (pinfunction "V+_7") (pintype "unspecified"))
      (node (ref "U24") (pin "7") (pinfunction "V+_7") (pintype "unspecified"))
      (node (ref "U27") (pin "7") (pinfunction "V+_7") (pintype "unspecified"))
      (node (ref "U28") (pin "7") (pinfunction "V+_7") (pintype "unspecified"))
      (node (ref "U30") (pin "7") (pinfunction "V+_7") (pintype "unspecified"))
      (node (ref "U32") (pin "7") (pinfunction "V+_7") (pintype "unspecified"))
      (node (ref "U4") (pin "7") (pinfunction "V+_7") (pintype "unspecified"))
      (node (ref "U6") (pin "7") (pinfunction "V+_7") (pintype "unspecified"))
      (node (ref "U8") (pin "7") (pinfunction "V+_7") (pintype "unspecified"))
    )
    (net (code "112") (name "VCC-5") (class "Default")
      (node (ref "C49") (pin "1") (pinfunction "1_1") (pintype "input"))
      (node (ref "C54") (pin "2") (pinfunction "2_2") (pintype "unspecified"))
      (node (ref "C57") (pin "2") (pinfunction "2_2") (pintype "unspecified"))
      (node (ref "H3") (pin "3") (pinfunction "3_3") (pintype "unspecified"))
      (node (ref "U41") (pin "2") (pinfunction "V-_2") (pintype "input"))
      (node (ref "U42") (pin "2") (pinfunction "V-_2") (pintype "input"))
    )
    (net (code "113") (name "VCC5") (class "Default")
      (node (ref "C48") (pin "2") (pinfunction "2_2") (pintype "unspecified"))
      (node (ref "C50") (pin "1") (pinfunction "1_1") (pintype "input"))
      (node (ref "C52") (pin "2") (pinfunction "2_2") (pintype "unspecified"))
      (node (ref "C53") (pin "2") (pinfunction "2_2") (pintype "input"))
      (node (ref "H3") (pin "1") (pinfunction "1_1") (pintype "unspecified"))
      (node (ref "U40") (pin "3") (pinfunction "ENABLE_3") (pintype "unspecified"))
      (node (ref "U40") (pin "4") (pinfunction "IN_4") (pintype "unspecified"))
      (node (ref "U41") (pin "5") (pinfunction "V+_5") (pintype "input"))
      (node (ref "U42") (pin "5") (pinfunction "V+_5") (pintype "input"))
    )
    (net (code "114") (name "unconnected-(CN1-Pad1)") (class "Default")
      (node (ref "CN1") (pin "1") (pinfunction "1_1") (pintype "unspecified"))
    )
    (net (code "115") (name "unconnected-(CN1-Pad2)") (class "Default")
      (node (ref "CN1") (pin "2") (pinfunction "2_2") (pintype "unspecified"))
    )
    (net (code "116") (name "unconnected-(CN1-Pad3)") (class "Default")
      (node (ref "CN1") (pin "3") (pinfunction "3_3") (pintype "unspecified"))
    )
    (net (code "117") (name "unconnected-(CN1-Pad4)") (class "Default")
      (node (ref "CN1") (pin "4") (pinfunction "4_4") (pintype "unspecified"))
    )
    (net (code "118") (name "unconnected-(CN1-Pad5)") (class "Default")
      (node (ref "CN1") (pin "5") (pinfunction "5_5") (pintype "unspecified"))
    )
    (net (code "119") (name "unconnected-(CN1-Pad6)") (class "Default")
      (node (ref "CN1") (pin "6") (pinfunction "6_6") (pintype "unspecified"))
    )
    (net (code "120") (name "unconnected-(CN1-Pad7)") (class "Default")
      (node (ref "CN1") (pin "7") (pinfunction "7_7") (pintype "unspecified"))
    )
    (net (code "121") (name "unconnected-(CN1-Pad8)") (class "Default")
      (node (ref "CN1") (pin "8") (pinfunction "8_8") (pintype "unspecified"))
    )
    (net (code "122") (name "unconnected-(CN1-Pad9)") (class "Default")
      (node (ref "CN1") (pin "9") (pinfunction "9_9") (pintype "unspecified"))
    )
    (net (code "123") (name "unconnected-(CN1-Pad10)") (class "Default")
      (node (ref "CN1") (pin "10") (pinfunction "10_10") (pintype "unspecified"))
    )
    (net (code "124") (name "unconnected-(CN1-Pad11)") (class "Default")
      (node (ref "CN1") (pin "11") (pinfunction "11_11") (pintype "unspecified"))
    )
    (net (code "125") (name "unconnected-(CN1-Pad12)") (class "Default")
      (node (ref "CN1") (pin "12") (pinfunction "12_12") (pintype "unspecified"))
    )
    (net (code "126") (name "unconnected-(CN1-Pad13)") (class "Default")
      (node (ref "CN1") (pin "13") (pinfunction "13_13") (pintype "unspecified"))
    )
    (net (code "127") (name "unconnected-(CN1-Pad14)") (class "Default")
      (node (ref "CN1") (pin "14") (pinfunction "14_14") (pintype "unspecified"))
    )
    (net (code "128") (name "unconnected-(CN1-Pad15)") (class "Default")
      (node (ref "CN1") (pin "15") (pinfunction "15_15") (pintype "unspecified"))
    )
    (net (code "129") (name "unconnected-(CN1-Pad16)") (class "Default")
      (node (ref "CN1") (pin "16") (pinfunction "16_16") (pintype "unspecified"))
    )
    (net (code "130") (name "unconnected-(CN1-Pad17)") (class "Default")
      (node (ref "CN1") (pin "17") (pinfunction "17_17") (pintype "unspecified"))
    )
    (net (code "131") (name "unconnected-(CN1-Pad18)") (class "Default")
      (node (ref "CN1") (pin "18") (pinfunction "18_18") (pintype "unspecified"))
    )
    (net (code "132") (name "unconnected-(CN1-Pad19)") (class "Default")
      (node (ref "CN1") (pin "19") (pinfunction "19_19") (pintype "unspecified"))
    )
    (net (code "133") (name "unconnected-(CN1-Pad20)") (class "Default")
      (node (ref "CN1") (pin "20") (pinfunction "20_20") (pintype "unspecified"))
    )
    (net (code "134") (name "unconnected-(CN1-Pad21)") (class "Default")
      (node (ref "CN1") (pin "21") (pinfunction "21_21") (pintype "unspecified"))
    )
    (net (code "135") (name "unconnected-(CN1-Pad22)") (class "Default")
      (node (ref "CN1") (pin "22") (pinfunction "22_22") (pintype "unspecified"))
    )
    (net (code "136") (name "unconnected-(CN1-Pad23)") (class "Default")
      (node (ref "CN1") (pin "23") (pinfunction "23_23") (pintype "unspecified"))
    )
    (net (code "137") (name "unconnected-(CN1-Pad24)") (class "Default")
      (node (ref "CN1") (pin "24") (pinfunction "24_24") (pintype "unspecified"))
    )
    (net (code "138") (name "unconnected-(CN2-Pad5)") (class "Default")
      (node (ref "CN2") (pin "5") (pinfunction "5_5") (pintype "unspecified"))
    )
    (net (code "139") (name "unconnected-(CN2-Pad6)") (class "Default")
      (node (ref "CN2") (pin "6") (pinfunction "6_6") (pintype "unspecified"))
    )
    (net (code "140") (name "unconnected-(CN2-Pad7)") (class "Default")
      (node (ref "CN2") (pin "7") (pinfunction "7_7") (pintype "unspecified"))
    )
    (net (code "141") (name "unconnected-(CN2-Pad8)") (class "Default")
      (node (ref "CN2") (pin "8") (pinfunction "8_8") (pintype "unspecified"))
    )
    (net (code "142") (name "unconnected-(CN2-Pad9)") (class "Default")
      (node (ref "CN2") (pin "9") (pinfunction "9_9") (pintype "unspecified"))
    )
    (net (code "143") (name "unconnected-(CN2-Pad10)") (class "Default")
      (node (ref "CN2") (pin "10") (pinfunction "10_10") (pintype "unspecified"))
    )
    (net (code "144") (name "unconnected-(CN2-Pad11)") (class "Default")
      (node (ref "CN2") (pin "11") (pinfunction "11_11") (pintype "unspecified"))
    )
    (net (code "145") (name "unconnected-(CN2-Pad12)") (class "Default")
      (node (ref "CN2") (pin "12") (pinfunction "12_12") (pintype "unspecified"))
    )
    (net (code "146") (name "unconnected-(CN2-Pad13)") (class "Default")
      (node (ref "CN2") (pin "13") (pinfunction "13_13") (pintype "unspecified"))
    )
    (net (code "147") (name "unconnected-(CN2-Pad15)") (class "Default")
      (node (ref "CN2") (pin "15") (pinfunction "15_15") (pintype "unspecified"))
    )
    (net (code "148") (name "unconnected-(CN2-Pad17)") (class "Default")
      (node (ref "CN2") (pin "17") (pinfunction "17_17") (pintype "unspecified"))
    )
    (net (code "149") (name "unconnected-(CN2-Pad19)") (class "Default")
      (node (ref "CN2") (pin "19") (pinfunction "19_19") (pintype "unspecified"))
    )
    (net (code "150") (name "unconnected-(CN2-Pad21)") (class "Default")
      (node (ref "CN2") (pin "21") (pinfunction "21_21") (pintype "unspecified"))
    )
    (net (code "151") (name "unconnected-(CN2-Pad22)") (class "Default")
      (node (ref "CN2") (pin "22") (pinfunction "22_22") (pintype "unspecified"))
    )
    (net (code "152") (name "unconnected-(CN2-Pad23)") (class "Default")
      (node (ref "CN2") (pin "23") (pinfunction "23_23") (pintype "unspecified"))
    )
    (net (code "153") (name "unconnected-(CN2-Pad24)") (class "Default")
      (node (ref "CN2") (pin "24") (pinfunction "24_24") (pintype "unspecified"))
    )
    (net (code "154") (name "unconnected-(U38-NC-Pad4)") (class "Default")
      (node (ref "U38") (pin "4") (pinfunction "NC_4") (pintype "input"))
    )
    (net (code "155") (name "unconnected-(U39-NC-Pad4)") (class "Default")
      (node (ref "U39") (pin "4") (pinfunction "NC_4") (pintype "input"))
    )
    (net (code "156") (name "unconnected-(U45-N{slash}C-Pad2)") (class "Default")
      (node (ref "U45") (pin "2") (pinfunction "N/C_2") (pintype "unspecified"))
    )
    (net (code "157") (name "unconnected-(U45-N{slash}C-Pad5)") (class "Default")
      (node (ref "U45") (pin "5") (pinfunction "N/C_5") (pintype "unspecified"))
    )
    (net (code "158") (name "unconnected-(U46-N{slash}C-Pad2)") (class "Default")
      (node (ref "U46") (pin "2") (pinfunction "N/C_2") (pintype "unspecified"))
    )
    (net (code "159") (name "unconnected-(U46-N{slash}C-Pad5)") (class "Default")
      (node (ref "U46") (pin "5") (pinfunction "N/C_5") (pintype "unspecified"))
    )
    (net (code "160") (name "unconnected-(U47-N{slash}C-Pad2)") (class "Default")
      (node (ref "U47") (pin "2") (pinfunction "N/C_2") (pintype "unspecified"))
    )
    (net (code "161") (name "unconnected-(U47-N{slash}C-Pad5)") (class "Default")
      (node (ref "U47") (pin "5") (pinfunction "N/C_5") (pintype "unspecified"))
    )
    (net (code "162") (name "unconnected-(U48-N{slash}C-Pad2)") (class "Default")
      (node (ref "U48") (pin "2") (pinfunction "N/C_2") (pintype "unspecified"))
    )
    (net (code "163") (name "unconnected-(U48-N{slash}C-Pad5)") (class "Default")
      (node (ref "U48") (pin "5") (pinfunction "N/C_5") (pintype "unspecified"))
    )
    (net (code "164") (name "unconnected-(U49-N{slash}C-Pad2)") (class "Default")
      (node (ref "U49") (pin "2") (pinfunction "N/C_2") (pintype "unspecified"))
    )
    (net (code "165") (name "unconnected-(U49-N{slash}C-Pad5)") (class "Default")
      (node (ref "U49") (pin "5") (pinfunction "N/C_5") (pintype "unspecified"))
    )
    (net (code "166") (name "unconnected-(U50-N{slash}C-Pad2)") (class "Default")
      (node (ref "U50") (pin "2") (pinfunction "N/C_2") (pintype "unspecified"))
    )
    (net (code "167") (name "unconnected-(U50-N{slash}C-Pad5)") (class "Default")
      (node (ref "U50") (pin "5") (pinfunction "N/C_5") (pintype "unspecified"))
    )
    (net (code "168") (name "unconnected-(U51-N{slash}C-Pad2)") (class "Default")
      (node (ref "U51") (pin "2") (pinfunction "N/C_2") (pintype "unspecified"))
    )
    (net (code "169") (name "unconnected-(U51-N{slash}C-Pad5)") (class "Default")
      (node (ref "U51") (pin "5") (pinfunction "N/C_5") (pintype "unspecified"))
    )
    (net (code "170") (name "unconnected-(U52-N{slash}C-Pad2)") (class "Default")
      (node (ref "U52") (pin "2") (pinfunction "N/C_2") (pintype "unspecified"))
    )
    (net (code "171") (name "unconnected-(U52-N{slash}C-Pad5)") (class "Default")
      (node (ref "U52") (pin "5") (pinfunction "N/C_5") (pintype "unspecified"))
    )
    (net (code "172") (name "unconnected-(U53-N{slash}C-Pad2)") (class "Default")
      (node (ref "U53") (pin "2") (pinfunction "N/C_2") (pintype "unspecified"))
    )
    (net (code "173") (name "unconnected-(U53-N{slash}C-Pad5)") (class "Default")
      (node (ref "U53") (pin "5") (pinfunction "N/C_5") (pintype "unspecified"))
    )
    (net (code "174") (name "unconnected-(U54-N{slash}C-Pad2)") (class "Default")
      (node (ref "U54") (pin "2") (pinfunction "N/C_2") (pintype "unspecified"))
    )
    (net (code "175") (name "unconnected-(U54-N{slash}C-Pad5)") (class "Default")
      (node (ref "U54") (pin "5") (pinfunction "N/C_5") (pintype "unspecified"))
    )
    (net (code "176") (name "unconnected-(U55-N{slash}C-Pad2)") (class "Default")
      (node (ref "U55") (pin "2") (pinfunction "N/C_2") (pintype "unspecified"))
    )
    (net (code "177") (name "unconnected-(U55-N{slash}C-Pad5)") (class "Default")
      (node (ref "U55") (pin "5") (pinfunction "N/C_5") (pintype "unspecified"))
    )
    (net (code "178") (name "unconnected-(U56-N{slash}C-Pad2)") (class "Default")
      (node (ref "U56") (pin "2") (pinfunction "N/C_2") (pintype "unspecified"))
    )
    (net (code "179") (name "unconnected-(U56-N{slash}C-Pad5)") (class "Default")
      (node (ref "U56") (pin "5") (pinfunction "N/C_5") (pintype "unspecified"))
    )
    (net (code "180") (name "unconnected-(U57-N{slash}C-Pad2)") (class "Default")
      (node (ref "U57") (pin "2") (pinfunction "N/C_2") (pintype "unspecified"))
    )
    (net (code "181") (name "unconnected-(U57-N{slash}C-Pad5)") (class "Default")
      (node (ref "U57") (pin "5") (pinfunction "N/C_5") (pintype "unspecified"))
    )
    (net (code "182") (name "unconnected-(U58-N{slash}C-Pad2)") (class "Default")
      (node (ref "U58") (pin "2") (pinfunction "N/C_2") (pintype "unspecified"))
    )
    (net (code "183") (name "unconnected-(U58-N{slash}C-Pad5)") (class "Default")
      (node (ref "U58") (pin "5") (pinfunction "N/C_5") (pintype "unspecified"))
    )
    (net (code "184") (name "unconnected-(U59-N{slash}C-Pad2)") (class "Default")
      (node (ref "U59") (pin "2") (pinfunction "N/C_2") (pintype "unspecified"))
    )
    (net (code "185") (name "unconnected-(U59-N{slash}C-Pad5)") (class "Default")
      (node (ref "U59") (pin "5") (pinfunction "N/C_5") (pintype "unspecified"))
    )
    (net (code "186") (name "unconnected-(U60-N{slash}C-Pad2)") (class "Default")
      (node (ref "U60") (pin "2") (pinfunction "N/C_2") (pintype "unspecified"))
    )
    (net (code "187") (name "unconnected-(U60-N{slash}C-Pad5)") (class "Default")
      (node (ref "U60") (pin "5") (pinfunction "N/C_5") (pintype "unspecified"))
    )
  )
)
